# 14_BoardPowerSupply.net
KiCad netlist of a schematic drawn in Altium Designer
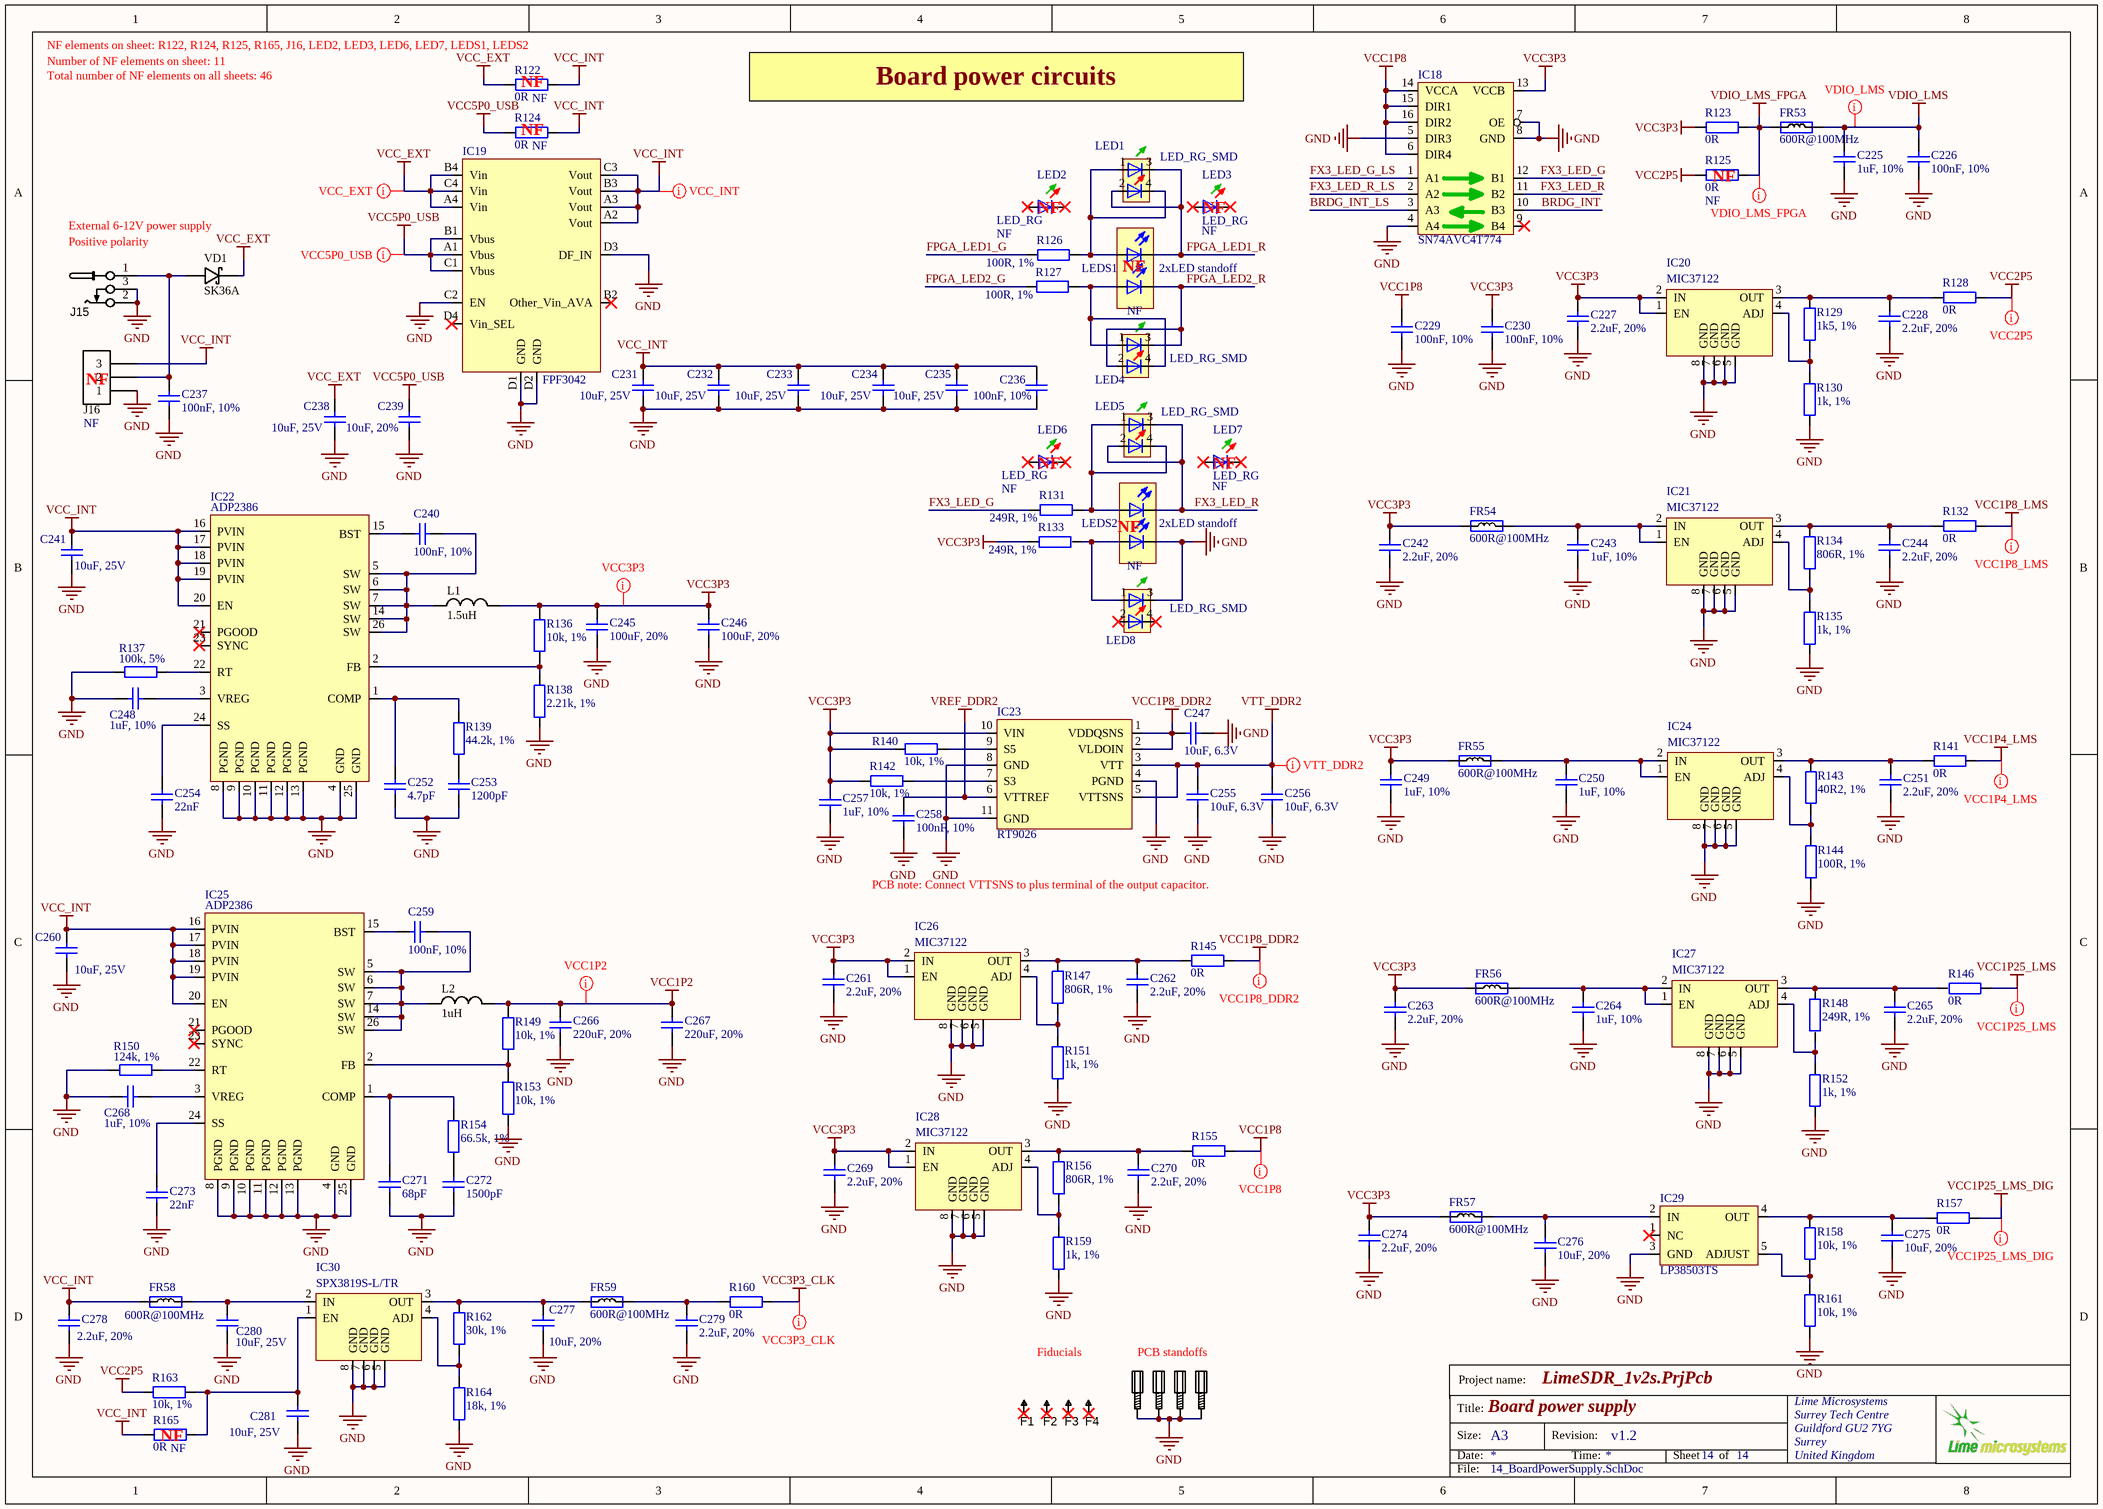
[diagram p0: 14_BoardPowerSupply.SchDoc]

(export (version "E")
  (design (tool "Eeschema 10.0.6"))
  (components
    (comp (ref "C225")
      (value "1uF, 10%")
      (footprint "CAP0402")
      (fields (field (name "MANUFACTURER") "TDK"))
      (libsource (lib "LimeMicroAltiumLib_schLib") (part "Cap_0402"))
    )
    (comp (ref "C226")
      (value "100nF, 10%")
      (footprint "CAP0402")
      (fields
        (field (name "MANUFACTURER") "Murata Electronics")
        (field (name "TOLERANCE") "10 %")
        (field (name "MANUFACTURER PART NUMBER") "GRM155R71C104KA88D")
      )
      (libsource (lib "LimeMicroAltiumLib_schLib") (part "Cap_0402"))
    )
    (comp (ref "C227")
      (value "2.2uF, 20%")
      (footprint "CAP0402")
      (fields (field (name "MANUFACTURER") "TDK Corporation") (field (name "TOLERANCE") "±20%"))
      (libsource (lib "LimeMicroAltiumLib_schLib") (part "Cap_0402"))
    )
    (comp (ref "C228")
      (value "2.2uF, 20%")
      (footprint "CAP0402")
      (fields (field (name "MANUFACTURER") "TDK Corporation") (field (name "TOLERANCE") "±20%"))
      (libsource (lib "LimeMicroAltiumLib_schLib") (part "Cap_0402"))
    )
    (comp (ref "C229")
      (value "100nF, 10%")
      (footprint "LimeMicroAltiumLib_pcbLib:CAP0402")
      (fields
        (field (name "MANUFACTURER") "Murata Electronics")
        (field (name "TOLERANCE") "10 %")
        (field (name "MANUFACTURER PART NUMBER") "GRM155R71C104KA88D")
      )
      (libsource (lib "LimeMicroAltiumLib_schLib") (part "Cap_0402"))
    )
    (comp (ref "C230")
      (value "100nF, 10%")
      (footprint "LimeMicroAltiumLib_pcbLib:CAP0402")
      (fields
        (field (name "MANUFACTURER") "Murata Electronics")
        (field (name "TOLERANCE") "10 %")
        (field (name "MANUFACTURER PART NUMBER") "GRM155R71C104KA88D")
      )
      (libsource (lib "LimeMicroAltiumLib_schLib") (part "Cap_0402"))
    )
    (comp (ref "C231")
      (value "10uF, 25V")
      (footprint "CAP0603")
      (fields
        (field (name "MANUFACTURER") "Murata Electronics North America")
        (field (name "MANUFACTURER PART NUMBER") "GRM188R61E106MA73D")
        (field (name "TOLERANCE") "±20%")
      )
      (libsource (lib "LimeMicroAltiumLib_schLib") (part "Cap_0603"))
    )
    (comp (ref "C232")
      (value "10uF, 25V")
      (footprint "CAP0603")
      (fields
        (field (name "MANUFACTURER") "Murata Electronics North America")
        (field (name "MANUFACTURER PART NUMBER") "GRM188R61E106MA73D")
        (field (name "TOLERANCE") "±20%")
      )
      (libsource (lib "LimeMicroAltiumLib_schLib") (part "Cap_0603"))
    )
    (comp (ref "C233")
      (value "10uF, 25V")
      (footprint "CAP0603")
      (fields
        (field (name "MANUFACTURER") "Murata Electronics North America")
        (field (name "MANUFACTURER PART NUMBER") "GRM188R61E106MA73D")
        (field (name "TOLERANCE") "±20%")
      )
      (libsource (lib "LimeMicroAltiumLib_schLib") (part "Cap_0603"))
    )
    (comp (ref "C234")
      (value "10uF, 25V")
      (footprint "CAP0603")
      (fields
        (field (name "MANUFACTURER") "Murata Electronics North America")
        (field (name "MANUFACTURER PART NUMBER") "GRM188R61E106MA73D")
        (field (name "TOLERANCE") "±20%")
      )
      (libsource (lib "LimeMicroAltiumLib_schLib") (part "Cap_0603"))
    )
    (comp (ref "C235")
      (value "10uF, 25V")
      (footprint "CAP0603")
      (fields
        (field (name "MANUFACTURER") "Murata Electronics North America")
        (field (name "MANUFACTURER PART NUMBER") "GRM188R61E106MA73D")
        (field (name "TOLERANCE") "±20%")
      )
      (libsource (lib "LimeMicroAltiumLib_schLib") (part "Cap_0603"))
    )
    (comp (ref "C236")
      (value "100nF, 10%")
      (footprint "CAP0402")
      (fields
        (field (name "MANUFACTURER") "Murata Electronics")
        (field (name "TOLERANCE") "10 %")
        (field (name "MANUFACTURER PART NUMBER") "GRM155R71C104KA88D")
      )
      (libsource (lib "LimeMicroAltiumLib_schLib") (part "Cap_0402"))
    )
    (comp (ref "C237")
      (value "100nF, 10%")
      (footprint "CAP0402")
      (fields
        (field (name "MANUFACTURER") "Murata Electronics")
        (field (name "TOLERANCE") "10 %")
        (field (name "MANUFACTURER PART NUMBER") "GRM155R71C104KA88D")
      )
      (libsource (lib "LimeMicroAltiumLib_schLib") (part "Cap_0402"))
    )
    (comp (ref "C238")
      (value "10uF, 25V")
      (footprint "CAP0603")
      (fields
        (field (name "MANUFACTURER") "Murata Electronics North America")
        (field (name "MANUFACTURER PART NUMBER") "GRM188R61E106MA73D")
        (field (name "TOLERANCE") "±20%")
      )
      (libsource (lib "LimeMicroAltiumLib_schLib") (part "Cap_0603"))
    )
    (comp (ref "C239")
      (value "10uF, 20%")
      (footprint "CAP0603")
      (fields (field (name "MANUFACTURER") "Yageo") (field (name "TOLERANCE") "±20%"))
      (libsource (lib "LimeMicroAltiumLib_schLib") (part "Cap_0603"))
    )
    (comp (ref "C240")
      (value "100nF, 10%")
      (footprint "CAP0402")
      (fields
        (field (name "MANUFACTURER") "Murata Electronics")
        (field (name "TOLERANCE") "10 %")
        (field (name "MANUFACTURER PART NUMBER") "GRM155R71C104KA88D")
      )
      (libsource (lib "LimeMicroAltiumLib_schLib") (part "Cap_0402"))
    )
    (comp (ref "C241")
      (value "10uF, 25V")
      (footprint "CAP0603")
      (fields
        (field (name "MANUFACTURER") "Murata Electronics North America")
        (field (name "MANUFACTURER PART NUMBER") "GRM188R61E106MA73D")
        (field (name "TOLERANCE") "±20%")
      )
      (libsource (lib "LimeMicroAltiumLib_schLib") (part "Cap_0603"))
    )
    (comp (ref "C242")
      (value "2.2uF, 20%")
      (footprint "CAP0402")
      (fields (field (name "MANUFACTURER") "TDK Corporation") (field (name "TOLERANCE") "±20%"))
      (libsource (lib "LimeMicroAltiumLib_schLib") (part "Cap_0402"))
    )
    (comp (ref "C243")
      (value "1uF, 10%")
      (footprint "CAP0402")
      (fields (field (name "MANUFACTURER") "TDK"))
      (libsource (lib "LimeMicroAltiumLib_schLib") (part "Cap_0402"))
    )
    (comp (ref "C244")
      (value "2.2uF, 20%")
      (footprint "CAP0402")
      (fields (field (name "MANUFACTURER") "TDK Corporation") (field (name "TOLERANCE") "±20%"))
      (libsource (lib "LimeMicroAltiumLib_schLib") (part "Cap_0402"))
    )
    (comp (ref "C245")
      (value "100uF, 20%")
      (footprint "CAP1206")
      (fields (field (name "MANUFACTURER") "Murata Electronics North America"))
      (libsource (lib "LimeFPGAboard_schLib") (part "Cap_1206"))
    )
    (comp (ref "C246")
      (value "100uF, 20%")
      (footprint "CAP1206")
      (fields (field (name "MANUFACTURER") "Murata Electronics North America"))
      (libsource (lib "LimeFPGAboard_schLib") (part "Cap_1206"))
    )
    (comp (ref "C247")
      (value "10uF, 6.3V")
      (footprint "CAP0603")
      (fields (field (name "TOLERANCE") "±20%") (field (name "MANUFACTURER") "Yageo"))
      (libsource (lib "LimeFPGAboard_schLib") (part "Cap_0603"))
    )
    (comp (ref "C248")
      (value "1uF, 10%")
      (footprint "CAP0402")
      (fields (field (name "MANUFACTURER") "TDK"))
      (libsource (lib "LimeMicroAltiumLib_schLib") (part "Cap_0402"))
    )
    (comp (ref "C249")
      (value "1uF, 10%")
      (footprint "CAP0402")
      (fields (field (name "MANUFACTURER") "TDK"))
      (libsource (lib "LimeMicroAltiumLib_schLib") (part "Cap_0402"))
    )
    (comp (ref "C250")
      (value "1uF, 10%")
      (footprint "CAP0402")
      (fields (field (name "MANUFACTURER") "TDK"))
      (libsource (lib "LimeMicroAltiumLib_schLib") (part "Cap_0402"))
    )
    (comp (ref "C251")
      (value "2.2uF, 20%")
      (footprint "CAP0402")
      (fields (field (name "MANUFACTURER") "TDK Corporation") (field (name "TOLERANCE") "±20%"))
      (libsource (lib "LimeMicroAltiumLib_schLib") (part "Cap_0402"))
    )
    (comp (ref "C252")
      (value "4.7pF")
      (footprint "CAP0402")
      (fields (field (name "MANUFACTURER") "Murata Electronics North America"))
      (libsource (lib "LimeMicroAltiumLib_schLib") (part "Cap_0402"))
    )
    (comp (ref "C253")
      (value "1200pF")
      (footprint "CAP0402")
      (fields (field (name "MANUFACTURER") "Kemet") (field (name "TOLERANCE") "±5%"))
      (libsource (lib "LimeMicroAltiumLib_schLib") (part "Cap_0402"))
    )
    (comp (ref "C254")
      (value "22nF")
      (footprint "CAP0402")
      (fields (field (name "TOLERANCE") "±10%") (field (name "MANUFACTURER") "Kemet"))
      (libsource (lib "LimeMicroAltiumLib_schLib") (part "Cap_0402"))
    )
    (comp (ref "C255")
      (value "10uF, 6.3V")
      (footprint "CAP0603")
      (fields (field (name "TOLERANCE") "±20%") (field (name "MANUFACTURER") "Yageo"))
      (libsource (lib "LimeFPGAboard_schLib") (part "Cap_0603"))
    )
    (comp (ref "C256")
      (value "10uF, 6.3V")
      (footprint "CAP0603")
      (fields (field (name "TOLERANCE") "±20%") (field (name "MANUFACTURER") "Yageo"))
      (libsource (lib "LimeFPGAboard_schLib") (part "Cap_0603"))
    )
    (comp (ref "C257")
      (value "1uF, 10%")
      (footprint "CAP0402")
      (fields (field (name "MANUFACTURER") "TDK"))
      (libsource (lib "LimeMicroAltiumLib_schLib") (part "Cap_0402"))
    )
    (comp (ref "C258")
      (value "100nF, 10%")
      (footprint "CAP0402")
      (fields
        (field (name "MANUFACTURER") "Murata Electronics")
        (field (name "TOLERANCE") "10 %")
        (field (name "MANUFACTURER PART NUMBER") "GRM155R71C104KA88D")
      )
      (libsource (lib "LimeMicroAltiumLib_schLib") (part "Cap_0402"))
    )
    (comp (ref "C259")
      (value "100nF, 10%")
      (footprint "CAP0402")
      (fields
        (field (name "MANUFACTURER") "Murata Electronics")
        (field (name "TOLERANCE") "10 %")
        (field (name "MANUFACTURER PART NUMBER") "GRM155R71C104KA88D")
      )
      (libsource (lib "LimeMicroAltiumLib_schLib") (part "Cap_0402"))
    )
    (comp (ref "C260")
      (value "10uF, 25V")
      (footprint "CAP0603")
      (fields
        (field (name "MANUFACTURER") "Murata Electronics North America")
        (field (name "MANUFACTURER PART NUMBER") "GRM188R61E106MA73D")
        (field (name "TOLERANCE") "±20%")
      )
      (libsource (lib "LimeMicroAltiumLib_schLib") (part "Cap_0603"))
    )
    (comp (ref "C261")
      (value "2.2uF, 20%")
      (footprint "CAP0402")
      (fields (field (name "MANUFACTURER") "TDK Corporation") (field (name "TOLERANCE") "±20%"))
      (libsource (lib "LimeMicroAltiumLib_schLib") (part "Cap_0402"))
    )
    (comp (ref "C262")
      (value "2.2uF, 20%")
      (footprint "CAP0402")
      (fields (field (name "MANUFACTURER") "TDK Corporation") (field (name "TOLERANCE") "±20%"))
      (libsource (lib "LimeMicroAltiumLib_schLib") (part "Cap_0402"))
    )
    (comp (ref "C263")
      (value "2.2uF, 20%")
      (footprint "CAP0402")
      (fields (field (name "MANUFACTURER") "TDK Corporation") (field (name "TOLERANCE") "±20%"))
      (libsource (lib "LimeMicroAltiumLib_schLib") (part "Cap_0402"))
    )
    (comp (ref "C264")
      (value "1uF, 10%")
      (footprint "CAP0402")
      (fields (field (name "MANUFACTURER") "TDK"))
      (libsource (lib "LimeMicroAltiumLib_schLib") (part "Cap_0402"))
    )
    (comp (ref "C265")
      (value "2.2uF, 20%")
      (footprint "CAP0402")
      (fields (field (name "MANUFACTURER") "TDK Corporation") (field (name "TOLERANCE") "±20%"))
      (libsource (lib "LimeMicroAltiumLib_schLib") (part "Cap_0402"))
    )
    (comp (ref "C266")
      (value "220uF, 20%")
      (footprint "CAP1206")
      (fields
        (field (name "MANUFACTURER") "Murata Electronics North America")
        (field (name "TOLERANCE") "±20%")
      )
      (libsource (lib "LimeFPGAboard_schLib") (part "Cap_1206"))
    )
    (comp (ref "C267")
      (value "220uF, 20%")
      (footprint "CAP1206")
      (fields
        (field (name "MANUFACTURER") "Murata Electronics North America")
        (field (name "TOLERANCE") "±20%")
      )
      (libsource (lib "LimeFPGAboard_schLib") (part "Cap_1206"))
    )
    (comp (ref "C268")
      (value "1uF, 10%")
      (footprint "CAP0402")
      (fields (field (name "MANUFACTURER") "TDK"))
      (libsource (lib "LimeMicroAltiumLib_schLib") (part "Cap_0402"))
    )
    (comp (ref "C269")
      (value "2.2uF, 20%")
      (footprint "CAP0402")
      (fields (field (name "MANUFACTURER") "TDK Corporation") (field (name "TOLERANCE") "±20%"))
      (libsource (lib "LimeMicroAltiumLib_schLib") (part "Cap_0402"))
    )
    (comp (ref "C270")
      (value "2.2uF, 20%")
      (footprint "CAP0402")
      (fields (field (name "MANUFACTURER") "TDK Corporation") (field (name "TOLERANCE") "±20%"))
      (libsource (lib "LimeMicroAltiumLib_schLib") (part "Cap_0402"))
    )
    (comp (ref "C271")
      (value "68pF")
      (footprint "CAP0402")
      (fields (field (name "TOLERANCE") "±1%") (field (name "MANUFACTURER") "Kemet"))
      (libsource (lib "LimeMicroAltiumLib_schLib") (part "Cap_0402"))
    )
    (comp (ref "C272")
      (value "1500pF")
      (footprint "CAP0402")
      (fields
        (field (name "MANUFACTURER") "Samsung Electro-Mechanics America, Inc.")
        (field (name "TOLERANCE") "±10%")
      )
      (libsource (lib "LimeMicroAltiumLib_schLib") (part "Cap_0402"))
    )
    (comp (ref "C273")
      (value "22nF")
      (footprint "CAP0402")
      (fields (field (name "TOLERANCE") "±10%") (field (name "MANUFACTURER") "Kemet"))
      (libsource (lib "LimeMicroAltiumLib_schLib") (part "Cap_0402"))
    )
    (comp (ref "C274")
      (value "2.2uF, 20%")
      (footprint "CAP0402")
      (fields (field (name "MANUFACTURER") "TDK Corporation") (field (name "TOLERANCE") "±20%"))
      (libsource (lib "LimeMicroAltiumLib_schLib") (part "Cap_0402"))
    )
    (comp (ref "C275")
      (value "10uF, 20%")
      (footprint "CAP0603")
      (fields (field (name "MANUFACTURER") "Yageo") (field (name "TOLERANCE") "±20%"))
      (libsource (lib "LimeMicroAltiumLib_schLib") (part "Cap_0603"))
    )
    (comp (ref "C276")
      (value "10uF, 20%")
      (footprint "CAP0603")
      (fields (field (name "MANUFACTURER") "Yageo") (field (name "TOLERANCE") "±20%"))
      (libsource (lib "LimeMicroAltiumLib_schLib") (part "Cap_0603"))
    )
    (comp (ref "C277")
      (value "10uF, 20%")
      (footprint "CAP0603")
      (fields (field (name "MANUFACTURER") "Yageo") (field (name "TOLERANCE") "±20%"))
      (libsource (lib "LimeMicroAltiumLib_schLib") (part "Cap_0603"))
    )
    (comp (ref "C278")
      (value "2.2uF, 20%")
      (footprint "CAP0402")
      (fields (field (name "MANUFACTURER") "TDK Corporation") (field (name "TOLERANCE") "±20%"))
      (libsource (lib "LimeMicroAltiumLib_schLib") (part "Cap_0402"))
    )
    (comp (ref "C279")
      (value "2.2uF, 20%")
      (footprint "CAP0402")
      (fields (field (name "MANUFACTURER") "TDK Corporation") (field (name "TOLERANCE") "±20%"))
      (libsource (lib "LimeMicroAltiumLib_schLib") (part "Cap_0402"))
    )
    (comp (ref "C280")
      (value "10uF, 25V")
      (footprint "CAP0603")
      (fields
        (field (name "MANUFACTURER") "Murata Electronics North America")
        (field (name "MANUFACTURER PART NUMBER") "GRM188R61E106MA73D")
        (field (name "TOLERANCE") "±20%")
      )
      (libsource (lib "LimeMicroAltiumLib_schLib") (part "Cap_0603"))
    )
    (comp (ref "C281")
      (value "10uF, 25V")
      (footprint "CAP0603")
      (fields
        (field (name "MANUFACTURER") "Murata Electronics North America")
        (field (name "MANUFACTURER PART NUMBER") "GRM188R61E106MA73D")
        (field (name "TOLERANCE") "±20%")
      )
      (libsource (lib "LimeMicroAltiumLib_schLib") (part "Cap_0603"))
    )
    (comp (ref "F1")
      (value "Fiducial")
      (footprint "Fiducial")
      (libsource (lib "VGTU_Altium_lib") (part "Fiducial"))
    )
    (comp (ref "F2")
      (value "Fiducial")
      (footprint "Fiducial")
      (libsource (lib "VGTU_Altium_lib") (part "Fiducial"))
    )
    (comp (ref "F3")
      (value "Fiducial")
      (footprint "Fiducial")
      (libsource (lib "VGTU_Altium_lib") (part "Fiducial"))
    )
    (comp (ref "F4")
      (value "Fiducial")
      (footprint "Fiducial")
      (libsource (lib "VGTU_Altium_lib") (part "Fiducial"))
    )
    (comp (ref "FR53")
      (value "600R@100MHz")
      (footprint "RES0805")
      (fields (field (name "MANUFACTURER") "TDK Corporation"))
      (libsource (lib "LimeMicroAltiumLib_schLib") (part "Ferrite"))
    )
    (comp (ref "FR54")
      (value "600R@100MHz")
      (footprint "RES0805")
      (fields (field (name "MANUFACTURER") "TDK Corporation"))
      (libsource (lib "LimeMicroAltiumLib_schLib") (part "Ferrite"))
    )
    (comp (ref "FR55")
      (value "600R@100MHz")
      (footprint "RES0805")
      (fields (field (name "MANUFACTURER") "TDK Corporation"))
      (libsource (lib "LimeMicroAltiumLib_schLib") (part "Ferrite"))
    )
    (comp (ref "FR56")
      (value "600R@100MHz")
      (footprint "RES0805")
      (fields (field (name "MANUFACTURER") "TDK Corporation"))
      (libsource (lib "LimeMicroAltiumLib_schLib") (part "Ferrite"))
    )
    (comp (ref "FR57")
      (value "600R@100MHz")
      (footprint "RES0805")
      (fields (field (name "MANUFACTURER") "TDK Corporation"))
      (libsource (lib "LimeMicroAltiumLib_schLib") (part "Ferrite"))
    )
    (comp (ref "FR58")
      (value "600R@100MHz")
      (footprint "RES0805")
      (fields (field (name "MANUFACTURER") "TDK Corporation"))
      (libsource (lib "LimeMicroAltiumLib_schLib") (part "Ferrite"))
    )
    (comp (ref "FR59")
      (value "600R@100MHz")
      (footprint "RES0805")
      (fields (field (name "MANUFACTURER") "TDK Corporation"))
      (libsource (lib "LimeMicroAltiumLib_schLib") (part "Ferrite"))
    )
    (comp (ref "IC18")
      (value "SN74AVC4T774")
      (footprint "LimeMicroAltiumLib_pcbLib:SN74AVC4T774")
      (fields (field (name "MANUFACTURER") "Texas Instruments"))
      (libsource (lib "LimeMicroAltiumLib_schLib") (part "SN74AVC4T774"))
    )
    (comp (ref "IC19")
      (value "FPF3042")
      (footprint "FPF3042")
      (fields (field (name "MANUFACTURER") "Fairchild Semiconductor"))
      (libsource (lib "LimeMicroAltiumLib_schLib") (part "FPF3042"))
    )
    (comp (ref "IC20")
      (value "MIC37122")
      (footprint "MIC37122YM TR_SO8")
      (fields (field (name "MANUFACTURER") "Microchip Technology"))
      (libsource (lib "LimeMicroAltiumLib_schLib") (part "MIC37122"))
    )
    (comp (ref "IC21")
      (value "MIC37122")
      (footprint "MIC37122YM TR_SO8")
      (fields (field (name "MANUFACTURER") "Microchip Technology"))
      (libsource (lib "LimeMicroAltiumLib_schLib") (part "MIC37122"))
    )
    (comp (ref "IC22")
      (value "ADP2386")
      (footprint "ADP2386")
      (fields
        (field (name "MANUFACTURER PART NUMBER") "ADP2386ACPZN-R7")
        (field (name "MANUFACTURER") "Analog Devices Inc.")
      )
      (libsource (lib "LimeMicroAltiumLib_schLib") (part "ADP2386"))
    )
    (comp (ref "IC23")
      (value "RT9026")
      (footprint "MSOP10")
      (fields (field (name "MANUFACTURER") "Richtek USA Inc."))
      (libsource (lib "LimeMicroAltiumLib_schLib") (part "RT9026"))
    )
    (comp (ref "IC24")
      (value "MIC37122")
      (footprint "MIC37122YM TR_SO8")
      (fields (field (name "MANUFACTURER") "Microchip Technology"))
      (libsource (lib "LimeMicroAltiumLib_schLib") (part "MIC37122"))
    )
    (comp (ref "IC25")
      (value "ADP2386")
      (footprint "ADP2386")
      (fields (field (name "MANUFACTURER") "Analog Devices Inc."))
      (libsource (lib "LimeMicroAltiumLib_schLib") (part "ADP2386"))
    )
    (comp (ref "IC26")
      (value "MIC37122")
      (footprint "MIC37122YM TR_SO8")
      (fields (field (name "MANUFACTURER") "Microchip Technology"))
      (libsource (lib "LimeMicroAltiumLib_schLib") (part "MIC37122"))
    )
    (comp (ref "IC27")
      (value "MIC37122")
      (footprint "MIC37122YM TR_SO8")
      (fields (field (name "MANUFACTURER") "Microchip Technology"))
      (libsource (lib "LimeMicroAltiumLib_schLib") (part "MIC37122"))
    )
    (comp (ref "IC28")
      (value "MIC37122")
      (footprint "MIC37122YM TR_SO8")
      (fields (field (name "MANUFACTURER") "Microchip Technology"))
      (libsource (lib "LimeMicroAltiumLib_schLib") (part "MIC37122"))
    )
    (comp (ref "IC29")
      (value "LP38503TS")
      (footprint "TO-263-5_v2")
      (fields
        (field (name "MANUFACTURER PART NUMBER") "LP38503TS-ADJ/NOPB")
        (field (name "MANUFACTURER") "Texas Instruments")
      )
      (libsource (lib "LimeMicroAltiumLib_schLib") (part "LP38503TS"))
    )
    (comp (ref "IC30")
      (value "SPX3819S-L/TR")
      (footprint "MIC37122YM TR_SO8")
      (fields (field (name "MANUFACTURER") "Exar Corporation"))
      (libsource (lib "LimeMicroAltiumLib_schLib") (part "MIC37122"))
    )
    (comp (ref "J15")
      (value "CONN_PWR_JACK_2.1x5.5mm")
      (footprint "CONN_PWR_JACK_v3")
      (description "Power Connector, THT, 2.1mm ID, 5.5mm OD")
      (fields (field (name "MANUFACTURER") "CUI Inc."))
      (libsource (lib "LimeFPGAboard_schLib") (part "CONN_PWR_JACK_2.1x5.5mm"))
    )
    (comp (ref "J16")
      (value "Header 3x1 pin")
      (footprint "HDR_1x3")
      (description "Header, 3-pin")
      (fields (field (name "ASSEMBLY INFO") "NF") (field (name "MANUFACTURER") "Amphenol FCI"))
      (libsource (lib "LimeMicroAltiumLib_schLib") (part "Header3P"))
    )
    (comp (ref "L1")
      (value "1.5uH")
      (footprint "FDVE1040_TOKO_INDUCTOR")
      (fields (field (name "MANUFACTURER") "Vishay Dale") (field (name "TOLERANCE") "±20%"))
      (libsource (lib "LimeMicroAltiumLib_schLib") (part "Inductor_0603"))
    )
    (comp (ref "L2")
      (value "1uH")
      (footprint "FDVE1040_TOKO_INDUCTOR")
      (fields (field (name "TOLERANCE") "±20%") (field (name "MANUFACTURER") "Vishay Dale"))
      (libsource (lib "LimeMicroAltiumLib_schLib") (part "Inductor_0603"))
    )
    (comp (ref "LED1")
      (value "LED_RG_SMD")
      (footprint "LED-2x0603")
      (fields (field (name "MANUFACTURER") "Avago Technologies US Inc."))
      (libsource (lib "LimeMicroAltiumLib_schLib") (part "LED_green_red_SMD"))
    )
    (comp (ref "LED2")
      (value "LED_RG")
      (fields
        (field (name "MANUFACTURER") "Visual Communications Company - VCC")
        (field (name "ASSEMBLY INFO") "NF")
      )
      (libsource (lib "LimeMicroAltiumLib_schLib") (part "LED_green_red"))
    )
    (comp (ref "LED3")
      (value "LED_RG")
      (fields
        (field (name "MANUFACTURER") "Visual Communications Company - VCC")
        (field (name "ASSEMBLY INFO") "NF")
      )
      (libsource (lib "LimeMicroAltiumLib_schLib") (part "LED_green_red"))
    )
    (comp (ref "LED4")
      (value "LED_RG_SMD")
      (footprint "LED-2x0603")
      (fields (field (name "MANUFACTURER") "Avago Technologies US Inc."))
      (libsource (lib "LimeMicroAltiumLib_schLib") (part "LED_green_red_SMD"))
    )
    (comp (ref "LED5")
      (value "LED_RG_SMD")
      (footprint "LED-2x0603")
      (fields (field (name "MANUFACTURER") "Avago Technologies US Inc."))
      (libsource (lib "LimeMicroAltiumLib_schLib") (part "LED_green_red_SMD"))
    )
    (comp (ref "LED6")
      (value "LED_RG")
      (fields
        (field (name "MANUFACTURER") "Visual Communications Company - VCC")
        (field (name "ASSEMBLY INFO") "NF")
      )
      (libsource (lib "LimeMicroAltiumLib_schLib") (part "LED_green_red"))
    )
    (comp (ref "LED7")
      (value "LED_RG")
      (fields
        (field (name "MANUFACTURER") "Visual Communications Company - VCC")
        (field (name "ASSEMBLY INFO") "NF")
      )
      (libsource (lib "LimeMicroAltiumLib_schLib") (part "LED_green_red"))
    )
    (comp (ref "LED8")
      (value "LED_RG_SMD")
      (footprint "LED-2x0603")
      (fields (field (name "MANUFACTURER") "Avago Technologies US Inc."))
      (libsource (lib "LimeMicroAltiumLib_schLib") (part "LED_green_red_SMD"))
    )
    (comp (ref "LEDS1")
      (value "2xLED standoff")
      (footprint "LED_STANDOFF_H-201C")
      (fields (field (name "MANUFACTURER") "Bivar Inc.") (field (name "ASSEMBLY INFO") "NF"))
      (libsource (lib "LimeMicroAltiumLib_schLib") (part "LEDx2_STANDOFF"))
    )
    (comp (ref "LEDS2")
      (value "2xLED standoff")
      (footprint "LED_STANDOFF_H-201C")
      (fields (field (name "MANUFACTURER") "Bivar Inc.") (field (name "ASSEMBLY INFO") "NF"))
      (libsource (lib "LimeMicroAltiumLib_schLib") (part "LEDx2_STANDOFF"))
    )
    (comp (ref "MECH1")
      (value "# pcs.")
      (footprint "PCB_standoff")
      (description "STANDOFF M/F MET 5MM HEX 10MM L")
      (fields
        (field (name "MANUFACTURER") "FIX&FASTEN")
        (field (name "MANUFACTURER PART NUMBER") "FIX-MAE-5TV")
      )
      (libsource (lib "LimeMicroAltiumLib_schLib") (part "STANDOFF_M-F_THREADED_M3x8x10mm_HEX_5mm dia"))
    )
    (comp (ref "MECH2")
      (value "# pcs.")
      (footprint "PCB_standoff")
      (description "STANDOFF M/F MET 5MM HEX 10MM L")
      (fields
        (field (name "MANUFACTURER") "FIX&FASTEN")
        (field (name "MANUFACTURER PART NUMBER") "FIX-MAE-5TV")
      )
      (libsource (lib "LimeMicroAltiumLib_schLib") (part "STANDOFF_M-F_THREADED_M3x8x10mm_HEX_5mm dia"))
    )
    (comp (ref "MECH3")
      (value "# pcs.")
      (footprint "PCB_standoff")
      (description "STANDOFF M/F MET 5MM HEX 10MM L")
      (fields
        (field (name "MANUFACTURER") "FIX&FASTEN")
        (field (name "MANUFACTURER PART NUMBER") "FIX-MAE-5TV")
      )
      (libsource (lib "LimeMicroAltiumLib_schLib") (part "STANDOFF_M-F_THREADED_M3x8x10mm_HEX_5mm dia"))
    )
    (comp (ref "MECH4")
      (value "# pcs.")
      (footprint "PCB_standoff")
      (description "STANDOFF M/F MET 5MM HEX 10MM L")
      (fields
        (field (name "MANUFACTURER") "FIX&FASTEN")
        (field (name "MANUFACTURER PART NUMBER") "FIX-MAE-5TV")
      )
      (libsource (lib "LimeMicroAltiumLib_schLib") (part "STANDOFF_M-F_THREADED_M3x8x10mm_HEX_5mm dia"))
    )
    (comp (ref "R122")
      (value "0R")
      (footprint "RES0402")
      (fields
        (field (name "ASSEMBLY INFO") "NF")
        (field (name "MANUFACTURER") "Yageo")
        (field (name "TOLERANCE") "Jumper")
      )
      (libsource (lib "LimeMicroAltiumLib_schLib") (part "Res_0402"))
    )
    (comp (ref "R123")
      (value "0R")
      (footprint "RES0402")
      (fields (field (name "MANUFACTURER") "Yageo") (field (name "TOLERANCE") "Jumper"))
      (libsource (lib "LimeMicroAltiumLib_schLib") (part "Res_0402"))
    )
    (comp (ref "R124")
      (value "0R")
      (footprint "RES0402")
      (fields
        (field (name "ASSEMBLY INFO") "NF")
        (field (name "MANUFACTURER") "Yageo")
        (field (name "TOLERANCE") "Jumper")
      )
      (libsource (lib "LimeMicroAltiumLib_schLib") (part "Res_0402"))
    )
    (comp (ref "R125")
      (value "0R")
      (footprint "RES0402")
      (fields
        (field (name "ASSEMBLY INFO") "NF")
        (field (name "MANUFACTURER") "Yageo")
        (field (name "TOLERANCE") "Jumper")
      )
      (libsource (lib "LimeMicroAltiumLib_schLib") (part "Res_0402"))
    )
    (comp (ref "R126")
      (value "100R, 1%")
      (footprint "RES0402")
      (fields (field (name "TOLERANCE") "±1%") (field (name "MANUFACTURER") "Stackpole Electronics Inc"))
      (libsource (lib "LimeMicroAltiumLib_schLib") (part "Res_0402"))
    )
    (comp (ref "R127")
      (value "100R, 1%")
      (footprint "RES0402")
      (fields (field (name "TOLERANCE") "±1%") (field (name "MANUFACTURER") "Stackpole Electronics Inc"))
      (libsource (lib "LimeMicroAltiumLib_schLib") (part "Res_0402"))
    )
    (comp (ref "R128")
      (value "0R")
      (footprint "RES0402")
      (fields (field (name "MANUFACTURER") "Yageo") (field (name "TOLERANCE") "Jumper"))
      (libsource (lib "LimeMicroAltiumLib_schLib") (part "Res_0402"))
    )
    (comp (ref "R129")
      (value "1k5, 1%")
      (footprint "RES0402")
      (fields (field (name "MANUFACTURER") "Yageo") (field (name "TOLERANCE") "±1%"))
      (libsource (lib "LimeMicroAltiumLib_schLib") (part "Res_0402"))
    )
    (comp (ref "R130")
      (value "1k, 1%")
      (footprint "RES0402")
      (fields (field (name "MANUFACTURER") "Stackpole Electronics Inc") (field (name "TOLERANCE") "±1%"))
      (libsource (lib "LimeMicroAltiumLib_schLib") (part "Res_0402"))
    )
    (comp (ref "R131")
      (value "249R, 1%")
      (footprint "RES0402")
      (fields (field (name "MANUFACTURER") "Stackpole Electronics Inc") (field (name "TOLERANCE") "±1%"))
      (libsource (lib "LimeMicroAltiumLib_schLib") (part "Res_0402"))
    )
    (comp (ref "R132")
      (value "0R")
      (footprint "RES0402")
      (fields (field (name "MANUFACTURER") "Yageo") (field (name "TOLERANCE") "Jumper"))
      (libsource (lib "LimeMicroAltiumLib_schLib") (part "Res_0402"))
    )
    (comp (ref "R133")
      (value "249R, 1%")
      (footprint "RES0402")
      (fields (field (name "MANUFACTURER") "Stackpole Electronics Inc") (field (name "TOLERANCE") "±1%"))
      (libsource (lib "LimeMicroAltiumLib_schLib") (part "Res_0402"))
    )
    (comp (ref "R134")
      (value "806R, 1%")
      (footprint "RES0402")
      (fields (field (name "TOLERANCE") "±1%") (field (name "MANUFACTURER") "Stackpole Electronics Inc"))
      (libsource (lib "LimeMicroAltiumLib_schLib") (part "Res_0402"))
    )
    (comp (ref "R135")
      (value "1k, 1%")
      (footprint "RES0402")
      (fields (field (name "MANUFACTURER") "Stackpole Electronics Inc") (field (name "TOLERANCE") "±1%"))
      (libsource (lib "LimeMicroAltiumLib_schLib") (part "Res_0402"))
    )
    (comp (ref "R136")
      (value "10k, 1%")
      (footprint "RES0402")
      (fields (field (name "MANUFACTURER") "Yageo") (field (name "TOLERANCE") "±1%"))
      (libsource (lib "LimeMicroAltiumLib_schLib") (part "Res_0402"))
    )
    (comp (ref "R137")
      (value "100k, 5%")
      (footprint "RES0402")
      (fields
        (field (name "MANUFACTURER") "Panasonic Electronic Components")
        (field (name "MANUFACTURER PART NUMBER") "ERJ-2GEJ104X")
        (field (name "TOLERANCE") "±5%")
      )
      (libsource (lib "LimeMicroAltiumLib_schLib") (part "Res_0402"))
    )
    (comp (ref "R138")
      (value "2.21k, 1%")
      (footprint "RES0402")
      (fields (field (name "MANUFACTURER") "Stackpole Electronics Inc.") (field (name "TOLERANCE") "±1%"))
      (libsource (lib "LimeMicroAltiumLib_schLib") (part "Res_0402"))
    )
    (comp (ref "R139")
      (value "44.2k, 1%")
      (footprint "RES0402")
      (fields
        (field (name "TOLERANCE") "±1%")
        (field (name "MANUFACTURER") "Panasonic Electronic Components")
      )
      (libsource (lib "LimeMicroAltiumLib_schLib") (part "Res_0402"))
    )
    (comp (ref "R140")
      (value "10k, 1%")
      (footprint "RES0402")
      (fields (field (name "MANUFACTURER") "Yageo") (field (name "TOLERANCE") "±1%"))
      (libsource (lib "LimeMicroAltiumLib_schLib") (part "Res_0402"))
    )
    (comp (ref "R141")
      (value "0R")
      (footprint "RES0402")
      (fields (field (name "MANUFACTURER") "Yageo") (field (name "TOLERANCE") "Jumper"))
      (libsource (lib "LimeMicroAltiumLib_schLib") (part "Res_0402"))
    )
    (comp (ref "R142")
      (value "10k, 1%")
      (footprint "RES0402")
      (fields (field (name "MANUFACTURER") "Yageo") (field (name "TOLERANCE") "±1%"))
      (libsource (lib "LimeMicroAltiumLib_schLib") (part "Res_0402"))
    )
    (comp (ref "R143")
      (value "40R2, 1%")
      (footprint "RES0402")
      (fields (field (name "MANUFACTURER") "Stackpole Electronics Inc") (field (name "TOLERANCE") "±1%"))
      (libsource (lib "LimeMicroAltiumLib_schLib") (part "Res_0402"))
    )
    (comp (ref "R144")
      (value "100R, 1%")
      (footprint "RES0402")
      (fields (field (name "TOLERANCE") "±1%") (field (name "MANUFACTURER") "Stackpole Electronics Inc"))
      (libsource (lib "LimeMicroAltiumLib_schLib") (part "Res_0402"))
    )
    (comp (ref "R145")
      (value "0R")
      (footprint "RES0402")
      (fields (field (name "MANUFACTURER") "Yageo") (field (name "TOLERANCE") "Jumper"))
      (libsource (lib "LimeMicroAltiumLib_schLib") (part "Res_0402"))
    )
    (comp (ref "R146")
      (value "0R")
      (footprint "RES0402")
      (fields (field (name "MANUFACTURER") "Yageo") (field (name "TOLERANCE") "Jumper"))
      (libsource (lib "LimeMicroAltiumLib_schLib") (part "Res_0402"))
    )
    (comp (ref "R147")
      (value "806R, 1%")
      (footprint "RES0402")
      (fields (field (name "TOLERANCE") "±1%") (field (name "MANUFACTURER") "Stackpole Electronics Inc"))
      (libsource (lib "LimeMicroAltiumLib_schLib") (part "Res_0402"))
    )
    (comp (ref "R148")
      (value "249R, 1%")
      (footprint "RES0402")
      (fields (field (name "MANUFACTURER") "Stackpole Electronics Inc") (field (name "TOLERANCE") "±1%"))
      (libsource (lib "LimeMicroAltiumLib_schLib") (part "Res_0402"))
    )
    (comp (ref "R149")
      (value "10k, 1%")
      (footprint "RES0402")
      (fields (field (name "MANUFACTURER") "Yageo") (field (name "TOLERANCE") "±1%"))
      (libsource (lib "LimeMicroAltiumLib_schLib") (part "Res_0402"))
    )
    (comp (ref "R150")
      (value "124k, 1%")
      (footprint "RES0402")
      (fields
        (field (name "MANUFACTURER") "Panasonic Electronic Components")
        (field (name "TOLERANCE") "±1%")
      )
      (libsource (lib "LimeMicroAltiumLib_schLib") (part "Res_0402"))
    )
    (comp (ref "R151")
      (value "1k, 1%")
      (footprint "RES0402")
      (fields (field (name "MANUFACTURER") "Stackpole Electronics Inc") (field (name "TOLERANCE") "±1%"))
      (libsource (lib "LimeMicroAltiumLib_schLib") (part "Res_0402"))
    )
    (comp (ref "R152")
      (value "1k, 1%")
      (footprint "RES0402")
      (fields (field (name "MANUFACTURER") "Stackpole Electronics Inc") (field (name "TOLERANCE") "±1%"))
      (libsource (lib "LimeMicroAltiumLib_schLib") (part "Res_0402"))
    )
    (comp (ref "R153")
      (value "10k, 1%")
      (footprint "RES0402")
      (fields (field (name "MANUFACTURER") "Yageo") (field (name "TOLERANCE") "±1%"))
      (libsource (lib "LimeMicroAltiumLib_schLib") (part "Res_0402"))
    )
    (comp (ref "R154")
      (value "66.5k, 1%")
      (footprint "RES0402")
      (fields
        (field (name "MANUFACTURER") "Panasonic Electronic Components")
        (field (name "TOLERANCE") "±1%")
      )
      (libsource (lib "LimeMicroAltiumLib_schLib") (part "Res_0402"))
    )
    (comp (ref "R155")
      (value "0R")
      (footprint "RES0402")
      (fields (field (name "MANUFACTURER") "Yageo") (field (name "TOLERANCE") "Jumper"))
      (libsource (lib "LimeMicroAltiumLib_schLib") (part "Res_0402"))
    )
    (comp (ref "R156")
      (value "806R, 1%")
      (footprint "RES0402")
      (fields (field (name "TOLERANCE") "±1%") (field (name "MANUFACTURER") "Stackpole Electronics Inc"))
      (libsource (lib "LimeMicroAltiumLib_schLib") (part "Res_0402"))
    )
    (comp (ref "R157")
      (value "0R")
      (footprint "RES0402")
      (fields (field (name "MANUFACTURER") "Yageo") (field (name "TOLERANCE") "Jumper"))
      (libsource (lib "LimeMicroAltiumLib_schLib") (part "Res_0402"))
    )
    (comp (ref "R158")
      (value "10k, 1%")
      (footprint "RES0402")
      (fields (field (name "MANUFACTURER") "Yageo") (field (name "TOLERANCE") "±1%"))
      (libsource (lib "LimeMicroAltiumLib_schLib") (part "Res_0402"))
    )
    (comp (ref "R159")
      (value "1k, 1%")
      (footprint "RES0402")
      (fields (field (name "MANUFACTURER") "Stackpole Electronics Inc") (field (name "TOLERANCE") "±1%"))
      (libsource (lib "LimeMicroAltiumLib_schLib") (part "Res_0402"))
    )
    (comp (ref "R160")
      (value "0R")
      (footprint "RES0402")
      (fields (field (name "MANUFACTURER") "Yageo") (field (name "TOLERANCE") "Jumper"))
      (libsource (lib "LimeMicroAltiumLib_schLib") (part "Res_0402"))
    )
    (comp (ref "R161")
      (value "10k, 1%")
      (footprint "RES0402")
      (fields (field (name "MANUFACTURER") "Yageo") (field (name "TOLERANCE") "±1%"))
      (libsource (lib "LimeMicroAltiumLib_schLib") (part "Res_0402"))
    )
    (comp (ref "R162")
      (value "30k, 1%")
      (footprint "RES0402")
      (fields
        (field (name "MANUFACTURER") "Vishay Dale")
        (field (name "MANUFACTURER PART NUMBER") "CRCW040230K0FKED")
        (field (name "TOLERANCE") "±1%")
      )
      (libsource (lib "LimeMicroAltiumLib_schLib") (part "Res_0402"))
    )
    (comp (ref "R163")
      (value "10k, 1%")
      (footprint "RES0402")
      (fields (field (name "MANUFACTURER") "Yageo") (field (name "TOLERANCE") "±1%"))
      (libsource (lib "LimeMicroAltiumLib_schLib") (part "Res_0402"))
    )
    (comp (ref "R164")
      (value "18k, 1%")
      (footprint "RES0402")
      (fields
        (field (name "TOLERANCE") "±1%")
        (field (name "MANUFACTURER PART NUMBER") "CRCW040218K0FKED")
        (field (name "MANUFACTURER") "Vishay Dale")
      )
      (libsource (lib "LimeMicroAltiumLib_schLib") (part "Res_0402"))
    )
    (comp (ref "R165")
      (value "0R")
      (footprint "RES0402")
      (fields
        (field (name "ASSEMBLY INFO") "NF")
        (field (name "MANUFACTURER") "Yageo")
        (field (name "TOLERANCE") "Jumper")
      )
      (libsource (lib "LimeMicroAltiumLib_schLib") (part "Res_0402"))
    )
    (comp (ref "VD1")
      (value "SK36A")
      (footprint "DIODE_SMB")
      (description "Diode Schottky SMD SOD-523F")
      (fields (field (name "MANUFACTURER") "Micro Commercial Co"))
      (libsource (lib "LimeMicroAltiumLib_schLib") (part "DIODE_SCHOTTKY_SOD-523F"))
    )
  )
  (nets
    (net (code "1") (name "/BRDG_INT") (class "Default")
      (node (ref "IC18") (pin "10") (pinfunction "B3_10") (pintype "passive"))
    )
    (net (code "2") (name "/BRDG_INT_LS") (class "Default")
      (node (ref "IC18") (pin "3") (pinfunction "A3_3") (pintype "passive"))
    )
    (net (code "3") (name "/FPGA_LED1_G") (class "Default")
      (node (ref "R126") (pin "1") (pinfunction "1_1") (pintype "passive"))
    )
    (net (code "4") (name "/FPGA_LED1_R") (class "Default")
      (node (ref "LED1") (pin "2") (pinfunction "2_2") (pintype "power_in"))
      (node (ref "LED1") (pin "3") (pinfunction "3_3") (pintype "power_in"))
      (node (ref "LEDS1") (pin "K1") (pinfunction "C_K1") (pintype "power_in"))
    )
    (net (code "5") (name "/FPGA_LED2_G") (class "Default")
      (node (ref "R127") (pin "1") (pinfunction "1_1") (pintype "passive"))
    )
    (net (code "6") (name "/FPGA_LED2_R") (class "Default")
      (node (ref "LED4") (pin "2") (pinfunction "2_2") (pintype "power_in"))
      (node (ref "LED4") (pin "3") (pinfunction "3_3") (pintype "power_in"))
      (node (ref "LEDS1") (pin "K2") (pinfunction "C_K2") (pintype "power_in"))
    )
    (net (code "7") (name "/FX3_LED_G") (class "Default")
      (node (ref "IC18") (pin "12") (pinfunction "B1_12") (pintype "passive"))
      (node (ref "R131") (pin "1") (pinfunction "1_1") (pintype "passive"))
    )
    (net (code "8") (name "/FX3_LED_G_LS") (class "Default")
      (node (ref "IC18") (pin "1") (pinfunction "A1_1") (pintype "passive"))
    )
    (net (code "9") (name "/FX3_LED_R") (class "Default")
      (node (ref "IC18") (pin "11") (pinfunction "B2_11") (pintype "passive"))
      (node (ref "LED5") (pin "2") (pinfunction "2_2") (pintype "power_in"))
      (node (ref "LED5") (pin "3") (pinfunction "3_3") (pintype "power_in"))
      (node (ref "LEDS2") (pin "K1") (pinfunction "C_K1") (pintype "power_in"))
    )
    (net (code "10") (name "/FX3_LED_R_LS") (class "Default")
      (node (ref "IC18") (pin "2") (pinfunction "A2_2") (pintype "passive"))
    )
    (net (code "11") (name "GND") (class "Default")
      (node (ref "C225") (pin "1") (pinfunction "1_1") (pintype "passive"))
      (node (ref "C226") (pin "2") (pinfunction "2_2") (pintype "passive"))
      (node (ref "C227") (pin "1") (pinfunction "1_1") (pintype "passive"))
      (node (ref "C228") (pin "1") (pinfunction "1_1") (pintype "passive"))
      (node (ref "C229") (pin "1") (pinfunction "1_1") (pintype "passive"))
      (node (ref "C230") (pin "1") (pinfunction "1_1") (pintype "passive"))
      (node (ref "C231") (pin "1") (pinfunction "1_1") (pintype "passive"))
      (node (ref "C232") (pin "1") (pinfunction "1_1") (pintype "passive"))
      (node (ref "C233") (pin "1") (pinfunction "1_1") (pintype "passive"))
      (node (ref "C234") (pin "1") (pinfunction "1_1") (pintype "passive"))
      (node (ref "C235") (pin "1") (pinfunction "1_1") (pintype "passive"))
      (node (ref "C236") (pin "2") (pinfunction "2_2") (pintype "passive"))
      (node (ref "C237") (pin "2") (pinfunction "2_2") (pintype "passive"))
      (node (ref "C238") (pin "1") (pinfunction "1_1") (pintype "passive"))
      (node (ref "C239") (pin "1") (pinfunction "1_1") (pintype "passive"))
      (node (ref "C241") (pin "1") (pinfunction "1_1") (pintype "passive"))
      (node (ref "C242") (pin "1") (pinfunction "1_1") (pintype "passive"))
      (node (ref "C243") (pin "1") (pinfunction "1_1") (pintype "passive"))
      (node (ref "C244") (pin "1") (pinfunction "1_1") (pintype "passive"))
      (node (ref "C245") (pin "1") (pinfunction "1_1") (pintype "passive"))
      (node (ref "C246") (pin "1") (pinfunction "1_1") (pintype "passive"))
      (node (ref "C247") (pin "1") (pinfunction "1_1") (pintype "passive"))
      (node (ref "C248") (pin "2") (pinfunction "2_2") (pintype "passive"))
      (node (ref "C249") (pin "1") (pinfunction "1_1") (pintype "passive"))
      (node (ref "C250") (pin "1") (pinfunction "1_1") (pintype "passive"))
      (node (ref "C251") (pin "1") (pinfunction "1_1") (pintype "passive"))
      (node (ref "C252") (pin "2") (pinfunction "2_2") (pintype "passive"))
      (node (ref "C253") (pin "2") (pinfunction "2_2") (pintype "passive"))
      (node (ref "C254") (pin "2") (pinfunction "2_2") (pintype "passive"))
      (node (ref "C255") (pin "1") (pinfunction "1_1") (pintype "passive"))
      (node (ref "C256") (pin "1") (pinfunction "1_1") (pintype "passive"))
      (node (ref "C257") (pin "1") (pinfunction "1_1") (pintype "passive"))
      (node (ref "C258") (pin "2") (pinfunction "2_2") (pintype "passive"))
      (node (ref "C260") (pin "1") (pinfunction "1_1") (pintype "passive"))
      (node (ref "C261") (pin "1") (pinfunction "1_1") (pintype "passive"))
      (node (ref "C262") (pin "1") (pinfunction "1_1") (pintype "passive"))
      (node (ref "C263") (pin "1") (pinfunction "1_1") (pintype "passive"))
      (node (ref "C264") (pin "1") (pinfunction "1_1") (pintype "passive"))
      (node (ref "C265") (pin "1") (pinfunction "1_1") (pintype "passive"))
      (node (ref "C266") (pin "1") (pinfunction "1_1") (pintype "passive"))
      (node (ref "C267") (pin "1") (pinfunction "1_1") (pintype "passive"))
      (node (ref "C268") (pin "2") (pinfunction "2_2") (pintype "passive"))
      (node (ref "C269") (pin "1") (pinfunction "1_1") (pintype "passive"))
      (node (ref "C270") (pin "1") (pinfunction "1_1") (pintype "passive"))
      (node (ref "C271") (pin "2") (pinfunction "2_2") (pintype "passive"))
      (node (ref "C272") (pin "2") (pinfunction "2_2") (pintype "passive"))
      (node (ref "C273") (pin "2") (pinfunction "2_2") (pintype "passive"))
      (node (ref "C274") (pin "1") (pinfunction "1_1") (pintype "passive"))
      (node (ref "C275") (pin "1") (pinfunction "1_1") (pintype "passive"))
      (node (ref "C276") (pin "1") (pinfunction "1_1") (pintype "passive"))
      (node (ref "C277") (pin "1") (pinfunction "1_1") (pintype "passive"))
      (node (ref "C278") (pin "1") (pinfunction "1_1") (pintype "passive"))
      (node (ref "C279") (pin "1") (pinfunction "1_1") (pintype "passive"))
      (node (ref "C280") (pin "1") (pinfunction "1_1") (pintype "passive"))
      (node (ref "C281") (pin "1") (pinfunction "1_1") (pintype "passive"))
      (node (ref "IC18") (pin "4") (pinfunction "A4_4") (pintype "passive"))
      (node (ref "IC18") (pin "5") (pinfunction "DIR3_5") (pintype "passive"))
      (node (ref "IC18") (pin "7") (pinfunction "OE_7") (pintype "passive"))
      (node (ref "IC18") (pin "8") (pinfunction "GND_8") (pintype "passive"))
      (node (ref "IC19") (pin "C2") (pinfunction "EN_C2") (pintype "passive"))
      (node (ref "IC19") (pin "D1") (pinfunction "GND_D1") (pintype "passive"))
      (node (ref "IC19") (pin "D2") (pinfunction "GND_D2") (pintype "passive"))
      (node (ref "IC19") (pin "D3") (pinfunction "DF_IN_D3") (pintype "passive"))
      (node (ref "IC20") (pin "5") (pinfunction "GND_5") (pintype "passive"))
      (node (ref "IC20") (pin "6") (pinfunction "GND_6") (pintype "passive"))
      (node (ref "IC20") (pin "7") (pinfunction "GND_7") (pintype "passive"))
      (node (ref "IC20") (pin "8") (pinfunction "GND_8") (pintype "passive"))
      (node (ref "IC21") (pin "5") (pinfunction "GND_5") (pintype "passive"))
      (node (ref "IC21") (pin "6") (pinfunction "GND_6") (pintype "passive"))
      (node (ref "IC21") (pin "7") (pinfunction "GND_7") (pintype "passive"))
      (node (ref "IC21") (pin "8") (pinfunction "GND_8") (pintype "passive"))
      (node (ref "IC22") (pin "10") (pinfunction "PGND_10") (pintype "passive"))
      (node (ref "IC22") (pin "11") (pinfunction "PGND_11") (pintype "passive"))
      (node (ref "IC22") (pin "12") (pinfunction "PGND_12") (pintype "passive"))
      (node (ref "IC22") (pin "13") (pinfunction "PGND_13") (pintype "passive"))
      (node (ref "IC22") (pin "25") (pinfunction "GND_25") (pintype "passive"))
      (node (ref "IC22") (pin "4") (pinfunction "GND_4") (pintype "passive"))
      (node (ref "IC22") (pin "8") (pinfunction "PGND_8") (pintype "passive"))
      (node (ref "IC22") (pin "9") (pinfunction "PGND_9") (pintype "passive"))
      (node (ref "IC23") (pin "11") (pinfunction "GND_11") (pintype "passive"))
      (node (ref "IC23") (pin "4") (pinfunction "PGND_4") (pintype "passive"))
      (node (ref "IC23") (pin "8") (pinfunction "GND_8") (pintype "passive"))
      (node (ref "IC24") (pin "5") (pinfunction "GND_5") (pintype "passive"))
      (node (ref "IC24") (pin "6") (pinfunction "GND_6") (pintype "passive"))
      (node (ref "IC24") (pin "7") (pinfunction "GND_7") (pintype "passive"))
      (node (ref "IC24") (pin "8") (pinfunction "GND_8") (pintype "passive"))
      (node (ref "IC25") (pin "10") (pinfunction "PGND_10") (pintype "passive"))
      (node (ref "IC25") (pin "11") (pinfunction "PGND_11") (pintype "passive"))
      (node (ref "IC25") (pin "12") (pinfunction "PGND_12") (pintype "passive"))
      (node (ref "IC25") (pin "13") (pinfunction "PGND_13") (pintype "passive"))
      (node (ref "IC25") (pin "25") (pinfunction "GND_25") (pintype "passive"))
      (node (ref "IC25") (pin "4") (pinfunction "GND_4") (pintype "passive"))
      (node (ref "IC25") (pin "8") (pinfunction "PGND_8") (pintype "passive"))
      (node (ref "IC25") (pin "9") (pinfunction "PGND_9") (pintype "passive"))
      (node (ref "IC26") (pin "5") (pinfunction "GND_5") (pintype "passive"))
      (node (ref "IC26") (pin "6") (pinfunction "GND_6") (pintype "passive"))
      (node (ref "IC26") (pin "7") (pinfunction "GND_7") (pintype "passive"))
      (node (ref "IC26") (pin "8") (pinfunction "GND_8") (pintype "passive"))
      (node (ref "IC27") (pin "5") (pinfunction "GND_5") (pintype "passive"))
      (node (ref "IC27") (pin "6") (pinfunction "GND_6") (pintype "passive"))
      (node (ref "IC27") (pin "7") (pinfunction "GND_7") (pintype "passive"))
      (node (ref "IC27") (pin "8") (pinfunction "GND_8") (pintype "passive"))
      (node (ref "IC28") (pin "5") (pinfunction "GND_5") (pintype "passive"))
      (node (ref "IC28") (pin "6") (pinfunction "GND_6") (pintype "passive"))
      (node (ref "IC28") (pin "7") (pinfunction "GND_7") (pintype "passive"))
      (node (ref "IC28") (pin "8") (pinfunction "GND_8") (pintype "passive"))
      (node (ref "IC29") (pin "3") (pinfunction "GND_3") (pintype "passive"))
      (node (ref "IC30") (pin "5") (pinfunction "GND_5") (pintype "passive"))
      (node (ref "IC30") (pin "6") (pinfunction "GND_6") (pintype "passive"))
      (node (ref "IC30") (pin "7") (pinfunction "GND_7") (pintype "passive"))
      (node (ref "IC30") (pin "8") (pinfunction "GND_8") (pintype "passive"))
      (node (ref "J15") (pin "2") (pinfunction "2_2") (pintype "passive"))
      (node (ref "J15") (pin "3") (pinfunction "3_3") (pintype "passive"))
      (node (ref "J16") (pin "1") (pinfunction "1_1") (pintype "passive"))
      (node (ref "LED8") (pin "3") (pinfunction "3_3") (pintype "power_in"))
      (node (ref "LEDS2") (pin "K2") (pinfunction "C_K2") (pintype "power_in"))
      (node (ref "MECH1") (pin "MH1") (pinfunction "MH1_MH1") (pintype "passive"))
      (node (ref "MECH2") (pin "MH1") (pinfunction "MH1_MH1") (pintype "passive"))
      (node (ref "MECH3") (pin "MH1") (pinfunction "MH1_MH1") (pintype "passive"))
      (node (ref "MECH4") (pin "MH1") (pinfunction "MH1_MH1") (pintype "passive"))
      (node (ref "R130") (pin "1") (pinfunction "1_1") (pintype "passive"))
      (node (ref "R135") (pin "1") (pinfunction "1_1") (pintype "passive"))
      (node (ref "R137") (pin "2") (pinfunction "2_2") (pintype "passive"))
      (node (ref "R138") (pin "1") (pinfunction "1_1") (pintype "passive"))
      (node (ref "R144") (pin "2") (pinfunction "2_2") (pintype "passive"))
      (node (ref "R150") (pin "2") (pinfunction "2_2") (pintype "passive"))
      (node (ref "R151") (pin "1") (pinfunction "1_1") (pintype "passive"))
      (node (ref "R152") (pin "1") (pinfunction "1_1") (pintype "passive"))
      (node (ref "R153") (pin "2") (pinfunction "2_2") (pintype "passive"))
      (node (ref "R159") (pin "1") (pinfunction "1_1") (pintype "passive"))
      (node (ref "R161") (pin "2") (pinfunction "2_2") (pintype "passive"))
      (node (ref "R164") (pin "1") (pinfunction "1_1") (pintype "passive"))
    )
    (net (code "12") (name "Net-(C237-Pad1)") (class "Default")
      (node (ref "C237") (pin "1") (pinfunction "1_1") (pintype "passive"))
      (node (ref "J15") (pin "1") (pinfunction "1_1") (pintype "passive"))
      (node (ref "J16") (pin "2") (pinfunction "2_2") (pintype "passive"))
      (node (ref "VD1") (pin "A") (pinfunction "A_A") (pintype "passive"))
    )
    (net (code "13") (name "Net-(C240-Pad2)") (class "Default")
      (node (ref "C240") (pin "2") (pinfunction "2_2") (pintype "passive"))
      (node (ref "IC22") (pin "14") (pinfunction "SW_14") (pintype "passive"))
      (node (ref "IC22") (pin "26") (pinfunction "SW_26") (pintype "passive"))
      (node (ref "IC22") (pin "5") (pinfunction "SW_5") (pintype "passive"))
      (node (ref "IC22") (pin "6") (pinfunction "SW_6") (pintype "passive"))
      (node (ref "IC22") (pin "7") (pinfunction "SW_7") (pintype "passive"))
      (node (ref "L1") (pin "1") (pinfunction "1_1") (pintype "passive"))
    )
    (net (code "14") (name "Net-(C253-Pad1)") (class "Default")
      (node (ref "C253") (pin "1") (pinfunction "1_1") (pintype "passive"))
      (node (ref "R139") (pin "1") (pinfunction "1_1") (pintype "passive"))
    )
    (net (code "15") (name "Net-(C259-Pad2)") (class "Default")
      (node (ref "C259") (pin "2") (pinfunction "2_2") (pintype "passive"))
      (node (ref "IC25") (pin "14") (pinfunction "SW_14") (pintype "passive"))
      (node (ref "IC25") (pin "26") (pinfunction "SW_26") (pintype "passive"))
      (node (ref "IC25") (pin "5") (pinfunction "SW_5") (pintype "passive"))
      (node (ref "IC25") (pin "6") (pinfunction "SW_6") (pintype "passive"))
      (node (ref "IC25") (pin "7") (pinfunction "SW_7") (pintype "passive"))
      (node (ref "L2") (pin "1") (pinfunction "1_1") (pintype "passive"))
    )
    (net (code "16") (name "Net-(C272-Pad1)") (class "Default")
      (node (ref "C272") (pin "1") (pinfunction "1_1") (pintype "passive"))
      (node (ref "R154") (pin "1") (pinfunction "1_1") (pintype "passive"))
    )
    (net (code "17") (name "Net-(C279-Pad2)") (class "Default")
      (node (ref "C279") (pin "2") (pinfunction "2_2") (pintype "passive"))
      (node (ref "FR59") (pin "2") (pinfunction "2_2") (pintype "passive"))
      (node (ref "R160") (pin "2") (pinfunction "2_2") (pintype "passive"))
    )
    (net (code "18") (name "Net-(IC20-ADJ)") (class "Default")
      (node (ref "IC20") (pin "4") (pinfunction "ADJ_4") (pintype "passive"))
      (node (ref "R129") (pin "2") (pinfunction "2_2") (pintype "passive"))
      (node (ref "R130") (pin "2") (pinfunction "2_2") (pintype "passive"))
    )
    (net (code "19") (name "Net-(IC20-OUT)") (class "Default")
      (node (ref "C228") (pin "2") (pinfunction "2_2") (pintype "passive"))
      (node (ref "IC20") (pin "3") (pinfunction "OUT_3") (pintype "passive"))
      (node (ref "R128") (pin "2") (pinfunction "2_2") (pintype "passive"))
      (node (ref "R129") (pin "1") (pinfunction "1_1") (pintype "passive"))
    )
    (net (code "20") (name "Net-(IC21-ADJ)") (class "Default")
      (node (ref "IC21") (pin "4") (pinfunction "ADJ_4") (pintype "passive"))
      (node (ref "R134") (pin "2") (pinfunction "2_2") (pintype "passive"))
      (node (ref "R135") (pin "2") (pinfunction "2_2") (pintype "passive"))
    )
    (net (code "21") (name "Net-(IC21-EN)") (class "Default")
      (node (ref "C243") (pin "2") (pinfunction "2_2") (pintype "passive"))
      (node (ref "FR54") (pin "2") (pinfunction "2_2") (pintype "passive"))
      (node (ref "IC21") (pin "1") (pinfunction "EN_1") (pintype "passive"))
      (node (ref "IC21") (pin "2") (pinfunction "IN_2") (pintype "passive"))
    )
    (net (code "22") (name "Net-(IC21-OUT)") (class "Default")
      (node (ref "C244") (pin "2") (pinfunction "2_2") (pintype "passive"))
      (node (ref "IC21") (pin "3") (pinfunction "OUT_3") (pintype "passive"))
      (node (ref "R132") (pin "2") (pinfunction "2_2") (pintype "passive"))
      (node (ref "R134") (pin "1") (pinfunction "1_1") (pintype "passive"))
    )
    (net (code "23") (name "Net-(IC22-BST)") (class "Default")
      (node (ref "C240") (pin "1") (pinfunction "1_1") (pintype "passive"))
      (node (ref "IC22") (pin "15") (pinfunction "BST_15") (pintype "passive"))
    )
    (net (code "24") (name "Net-(IC22-COMP)") (class "Default")
      (node (ref "C252") (pin "1") (pinfunction "1_1") (pintype "passive"))
      (node (ref "IC22") (pin "1") (pinfunction "COMP_1") (pintype "passive"))
      (node (ref "R139") (pin "2") (pinfunction "2_2") (pintype "passive"))
    )
    (net (code "25") (name "Net-(IC22-FB)") (class "Default")
      (node (ref "IC22") (pin "2") (pinfunction "FB_2") (pintype "passive"))
      (node (ref "R136") (pin "2") (pinfunction "2_2") (pintype "passive"))
      (node (ref "R138") (pin "2") (pinfunction "2_2") (pintype "passive"))
    )
    (net (code "26") (name "Net-(IC22-RT)") (class "Default")
      (node (ref "IC22") (pin "22") (pinfunction "RT_22") (pintype "passive"))
      (node (ref "R137") (pin "1") (pinfunction "1_1") (pintype "passive"))
    )
    (net (code "27") (name "Net-(IC22-SS)") (class "Default")
      (node (ref "C254") (pin "1") (pinfunction "1_1") (pintype "passive"))
      (node (ref "IC22") (pin "24") (pinfunction "SS_24") (pintype "passive"))
    )
    (net (code "28") (name "Net-(IC22-VREG)") (class "Default")
      (node (ref "C248") (pin "1") (pinfunction "1_1") (pintype "passive"))
      (node (ref "IC22") (pin "3") (pinfunction "VREG_3") (pintype "passive"))
    )
    (net (code "29") (name "Net-(IC23-S3)") (class "Default")
      (node (ref "IC23") (pin "7") (pinfunction "S3_7") (pintype "passive"))
      (node (ref "R142") (pin "2") (pinfunction "2_2") (pintype "passive"))
    )
    (net (code "30") (name "Net-(IC23-S5)") (class "Default")
      (node (ref "IC23") (pin "9") (pinfunction "S5_9") (pintype "passive"))
      (node (ref "R140") (pin "2") (pinfunction "2_2") (pintype "passive"))
    )
    (net (code "31") (name "Net-(IC24-ADJ)") (class "Default")
      (node (ref "IC24") (pin "4") (pinfunction "ADJ_4") (pintype "passive"))
      (node (ref "R143") (pin "2") (pinfunction "2_2") (pintype "passive"))
      (node (ref "R144") (pin "1") (pinfunction "1_1") (pintype "passive"))
    )
    (net (code "32") (name "Net-(IC24-EN)") (class "Default")
      (node (ref "C250") (pin "2") (pinfunction "2_2") (pintype "passive"))
      (node (ref "FR55") (pin "2") (pinfunction "2_2") (pintype "passive"))
      (node (ref "IC24") (pin "1") (pinfunction "EN_1") (pintype "passive"))
      (node (ref "IC24") (pin "2") (pinfunction "IN_2") (pintype "passive"))
    )
    (net (code "33") (name "Net-(IC24-OUT)") (class "Default")
      (node (ref "C251") (pin "2") (pinfunction "2_2") (pintype "passive"))
      (node (ref "IC24") (pin "3") (pinfunction "OUT_3") (pintype "passive"))
      (node (ref "R141") (pin "2") (pinfunction "2_2") (pintype "passive"))
      (node (ref "R143") (pin "1") (pinfunction "1_1") (pintype "passive"))
    )
    (net (code "34") (name "Net-(IC25-BST)") (class "Default")
      (node (ref "C259") (pin "1") (pinfunction "1_1") (pintype "passive"))
      (node (ref "IC25") (pin "15") (pinfunction "BST_15") (pintype "passive"))
    )
    (net (code "35") (name "Net-(IC25-COMP)") (class "Default")
      (node (ref "C271") (pin "1") (pinfunction "1_1") (pintype "passive"))
      (node (ref "IC25") (pin "1") (pinfunction "COMP_1") (pintype "passive"))
      (node (ref "R154") (pin "2") (pinfunction "2_2") (pintype "passive"))
    )
    (net (code "36") (name "Net-(IC25-FB)") (class "Default")
      (node (ref "IC25") (pin "2") (pinfunction "FB_2") (pintype "passive"))
      (node (ref "R149") (pin "2") (pinfunction "2_2") (pintype "passive"))
      (node (ref "R153") (pin "1") (pinfunction "1_1") (pintype "passive"))
    )
    (net (code "37") (name "Net-(IC25-RT)") (class "Default")
      (node (ref "IC25") (pin "22") (pinfunction "RT_22") (pintype "passive"))
      (node (ref "R150") (pin "1") (pinfunction "1_1") (pintype "passive"))
    )
    (net (code "38") (name "Net-(IC25-SS)") (class "Default")
      (node (ref "C273") (pin "1") (pinfunction "1_1") (pintype "passive"))
      (node (ref "IC25") (pin "24") (pinfunction "SS_24") (pintype "passive"))
    )
    (net (code "39") (name "Net-(IC25-VREG)") (class "Default")
      (node (ref "C268") (pin "1") (pinfunction "1_1") (pintype "passive"))
      (node (ref "IC25") (pin "3") (pinfunction "VREG_3") (pintype "passive"))
    )
    (net (code "40") (name "Net-(IC26-ADJ)") (class "Default")
      (node (ref "IC26") (pin "4") (pinfunction "ADJ_4") (pintype "passive"))
      (node (ref "R147") (pin "2") (pinfunction "2_2") (pintype "passive"))
      (node (ref "R151") (pin "2") (pinfunction "2_2") (pintype "passive"))
    )
    (net (code "41") (name "Net-(IC26-OUT)") (class "Default")
      (node (ref "C262") (pin "2") (pinfunction "2_2") (pintype "passive"))
      (node (ref "IC26") (pin "3") (pinfunction "OUT_3") (pintype "passive"))
      (node (ref "R145") (pin "2") (pinfunction "2_2") (pintype "passive"))
      (node (ref "R147") (pin "1") (pinfunction "1_1") (pintype "passive"))
    )
    (net (code "42") (name "Net-(IC27-ADJ)") (class "Default")
      (node (ref "IC27") (pin "4") (pinfunction "ADJ_4") (pintype "passive"))
      (node (ref "R148") (pin "2") (pinfunction "2_2") (pintype "passive"))
      (node (ref "R152") (pin "2") (pinfunction "2_2") (pintype "passive"))
    )
    (net (code "43") (name "Net-(IC27-EN)") (class "Default")
      (node (ref "C264") (pin "2") (pinfunction "2_2") (pintype "passive"))
      (node (ref "FR56") (pin "2") (pinfunction "2_2") (pintype "passive"))
      (node (ref "IC27") (pin "1") (pinfunction "EN_1") (pintype "passive"))
      (node (ref "IC27") (pin "2") (pinfunction "IN_2") (pintype "passive"))
    )
    (net (code "44") (name "Net-(IC27-OUT)") (class "Default")
      (node (ref "C265") (pin "2") (pinfunction "2_2") (pintype "passive"))
      (node (ref "IC27") (pin "3") (pinfunction "OUT_3") (pintype "passive"))
      (node (ref "R146") (pin "2") (pinfunction "2_2") (pintype "passive"))
      (node (ref "R148") (pin "1") (pinfunction "1_1") (pintype "passive"))
    )
    (net (code "45") (name "Net-(IC28-ADJ)") (class "Default")
      (node (ref "IC28") (pin "4") (pinfunction "ADJ_4") (pintype "passive"))
      (node (ref "R156") (pin "2") (pinfunction "2_2") (pintype "passive"))
      (node (ref "R159") (pin "2") (pinfunction "2_2") (pintype "passive"))
    )
    (net (code "46") (name "Net-(IC28-OUT)") (class "Default")
      (node (ref "C270") (pin "2") (pinfunction "2_2") (pintype "passive"))
      (node (ref "IC28") (pin "3") (pinfunction "OUT_3") (pintype "passive"))
      (node (ref "R155") (pin "2") (pinfunction "2_2") (pintype "passive"))
      (node (ref "R156") (pin "1") (pinfunction "1_1") (pintype "passive"))
    )
    (net (code "47") (name "Net-(IC29-ADJUST)") (class "Default")
      (node (ref "IC29") (pin "5") (pinfunction "ADJUST_5") (pintype "passive"))
      (node (ref "R158") (pin "2") (pinfunction "2_2") (pintype "passive"))
      (node (ref "R161") (pin "1") (pinfunction "1_1") (pintype "passive"))
    )
    (net (code "48") (name "Net-(IC29-IN)") (class "Default")
      (node (ref "C276") (pin "2") (pinfunction "2_2") (pintype "passive"))
      (node (ref "FR57") (pin "2") (pinfunction "2_2") (pintype "passive"))
      (node (ref "IC29") (pin "2") (pinfunction "IN_2") (pintype "passive"))
    )
    (net (code "49") (name "Net-(IC29-OUT)") (class "Default")
      (node (ref "C275") (pin "2") (pinfunction "2_2") (pintype "passive"))
      (node (ref "IC29") (pin "4") (pinfunction "OUT_4") (pintype "passive"))
      (node (ref "R157") (pin "2") (pinfunction "2_2") (pintype "passive"))
      (node (ref "R158") (pin "1") (pinfunction "1_1") (pintype "passive"))
    )
    (net (code "50") (name "Net-(IC30-ADJ)") (class "Default")
      (node (ref "IC30") (pin "4") (pinfunction "ADJ_4") (pintype "passive"))
      (node (ref "R162") (pin "2") (pinfunction "2_2") (pintype "passive"))
      (node (ref "R164") (pin "2") (pinfunction "2_2") (pintype "passive"))
    )
    (net (code "51") (name "Net-(IC30-EN)") (class "Default")
      (node (ref "C281") (pin "2") (pinfunction "2_2") (pintype "passive"))
      (node (ref "IC30") (pin "1") (pinfunction "EN_1") (pintype "passive"))
      (node (ref "R163") (pin "2") (pinfunction "2_2") (pintype "passive"))
      (node (ref "R165") (pin "1") (pinfunction "1_1") (pintype "passive"))
    )
    (net (code "52") (name "Net-(IC30-IN)") (class "Default")
      (node (ref "C280") (pin "2") (pinfunction "2_2") (pintype "passive"))
      (node (ref "FR58") (pin "2") (pinfunction "2_2") (pintype "passive"))
      (node (ref "IC30") (pin "2") (pinfunction "IN_2") (pintype "passive"))
    )
    (net (code "53") (name "Net-(IC30-OUT)") (class "Default")
      (node (ref "C277") (pin "2") (pinfunction "2_2") (pintype "passive"))
      (node (ref "FR59") (pin "1") (pinfunction "1_1") (pintype "passive"))
      (node (ref "IC30") (pin "3") (pinfunction "OUT_3") (pintype "passive"))
      (node (ref "R162") (pin "1") (pinfunction "1_1") (pintype "passive"))
    )
    (net (code "54") (name "Net-(LED1-Pad1)") (class "Default")
      (node (ref "LED1") (pin "1") (pinfunction "1_1") (pintype "power_in"))
      (node (ref "LED1") (pin "4") (pinfunction "4_4") (pintype "power_in"))
      (node (ref "LEDS1") (pin "A1") (pinfunction "A_A1") (pintype "power_in"))
      (node (ref "R126") (pin "2") (pinfunction "2_2") (pintype "passive"))
    )
    (net (code "55") (name "Net-(LED4-Pad1)") (class "Default")
      (node (ref "LED4") (pin "1") (pinfunction "1_1") (pintype "power_in"))
      (node (ref "LED4") (pin "4") (pinfunction "4_4") (pintype "power_in"))
      (node (ref "LEDS1") (pin "A2") (pinfunction "A_A2") (pintype "power_in"))
      (node (ref "R127") (pin "2") (pinfunction "2_2") (pintype "passive"))
    )
    (net (code "56") (name "Net-(LED5-Pad1)") (class "Default")
      (node (ref "LED5") (pin "1") (pinfunction "1_1") (pintype "power_in"))
      (node (ref "LED5") (pin "4") (pinfunction "4_4") (pintype "power_in"))
      (node (ref "LEDS2") (pin "A1") (pinfunction "A_A1") (pintype "power_in"))
      (node (ref "R131") (pin "2") (pinfunction "2_2") (pintype "passive"))
    )
    (net (code "57") (name "Net-(LED8-Pad1)") (class "Default")
      (node (ref "LED8") (pin "1") (pinfunction "1_1") (pintype "power_in"))
      (node (ref "LEDS2") (pin "A2") (pinfunction "A_A2") (pintype "power_in"))
      (node (ref "R133") (pin "2") (pinfunction "2_2") (pintype "passive"))
    )
    (net (code "58") (name "VCC1P2") (class "Default")
      (node (ref "C266") (pin "2") (pinfunction "2_2") (pintype "passive"))
      (node (ref "C267") (pin "2") (pinfunction "2_2") (pintype "passive"))
      (node (ref "L2") (pin "2") (pinfunction "2_2") (pintype "passive"))
      (node (ref "R149") (pin "1") (pinfunction "1_1") (pintype "passive"))
    )
    (net (code "59") (name "VCC1P4_LMS") (class "Default")
      (node (ref "R141") (pin "1") (pinfunction "1_1") (pintype "passive"))
    )
    (net (code "60") (name "VCC1P8") (class "Default")
      (node (ref "C229") (pin "2") (pinfunction "2_2") (pintype "passive"))
      (node (ref "IC18") (pin "14") (pinfunction "VCCA_14") (pintype "passive"))
      (node (ref "IC18") (pin "15") (pinfunction "DIR1_15") (pintype "passive"))
      (node (ref "IC18") (pin "16") (pinfunction "DIR2_16") (pintype "passive"))
      (node (ref "IC18") (pin "6") (pinfunction "DIR4_6") (pintype "passive"))
      (node (ref "R155") (pin "1") (pinfunction "1_1") (pintype "passive"))
    )
    (net (code "61") (name "VCC1P8_DDR2") (class "Default")
      (node (ref "C247") (pin "2") (pinfunction "2_2") (pintype "passive"))
      (node (ref "IC23") (pin "1") (pinfunction "VDDQSNS_1") (pintype "passive"))
      (node (ref "IC23") (pin "2") (pinfunction "VLDOIN_2") (pintype "passive"))
      (node (ref "R145") (pin "1") (pinfunction "1_1") (pintype "passive"))
    )
    (net (code "62") (name "VCC1P8_LMS") (class "Default")
      (node (ref "R132") (pin "1") (pinfunction "1_1") (pintype "passive"))
    )
    (net (code "63") (name "VCC1P25_LMS") (class "Default")
      (node (ref "R146") (pin "1") (pinfunction "1_1") (pintype "passive"))
    )
    (net (code "64") (name "VCC1P25_LMS_DIG") (class "Default")
      (node (ref "R157") (pin "1") (pinfunction "1_1") (pintype "passive"))
    )
    (net (code "65") (name "VCC2P5") (class "Default")
      (node (ref "R125") (pin "2") (pinfunction "2_2") (pintype "passive"))
      (node (ref "R128") (pin "1") (pinfunction "1_1") (pintype "passive"))
      (node (ref "R163") (pin "1") (pinfunction "1_1") (pintype "passive"))
    )
    (net (code "66") (name "VCC3P3") (class "Default")
      (node (ref "C227") (pin "2") (pinfunction "2_2") (pintype "passive"))
      (node (ref "C230") (pin "2") (pinfunction "2_2") (pintype "passive"))
      (node (ref "C242") (pin "2") (pinfunction "2_2") (pintype "passive"))
      (node (ref "C245") (pin "2") (pinfunction "2_2") (pintype "passive"))
      (node (ref "C246") (pin "2") (pinfunction "2_2") (pintype "passive"))
      (node (ref "C249") (pin "2") (pinfunction "2_2") (pintype "passive"))
      (node (ref "C257") (pin "2") (pinfunction "2_2") (pintype "passive"))
      (node (ref "C261") (pin "2") (pinfunction "2_2") (pintype "passive"))
      (node (ref "C263") (pin "2") (pinfunction "2_2") (pintype "passive"))
      (node (ref "C269") (pin "2") (pinfunction "2_2") (pintype "passive"))
      (node (ref "C274") (pin "2") (pinfunction "2_2") (pintype "passive"))
      (node (ref "FR54") (pin "1") (pinfunction "1_1") (pintype "passive"))
      (node (ref "FR55") (pin "1") (pinfunction "1_1") (pintype "passive"))
      (node (ref "FR56") (pin "1") (pinfunction "1_1") (pintype "passive"))
      (node (ref "FR57") (pin "1") (pinfunction "1_1") (pintype "passive"))
      (node (ref "IC18") (pin "13") (pinfunction "VCCB_13") (pintype "passive"))
      (node (ref "IC20") (pin "1") (pinfunction "EN_1") (pintype "passive"))
      (node (ref "IC20") (pin "2") (pinfunction "IN_2") (pintype "passive"))
      (node (ref "IC23") (pin "10") (pinfunction "VIN_10") (pintype "passive"))
      (node (ref "IC26") (pin "1") (pinfunction "EN_1") (pintype "passive"))
      (node (ref "IC26") (pin "2") (pinfunction "IN_2") (pintype "passive"))
      (node (ref "IC28") (pin "1") (pinfunction "EN_1") (pintype "passive"))
      (node (ref "IC28") (pin "2") (pinfunction "IN_2") (pintype "passive"))
      (node (ref "L1") (pin "2") (pinfunction "2_2") (pintype "passive"))
      (node (ref "R123") (pin "2") (pinfunction "2_2") (pintype "passive"))
      (node (ref "R133") (pin "1") (pinfunction "1_1") (pintype "passive"))
      (node (ref "R136") (pin "1") (pinfunction "1_1") (pintype "passive"))
      (node (ref "R140") (pin "1") (pinfunction "1_1") (pintype "passive"))
      (node (ref "R142") (pin "1") (pinfunction "1_1") (pintype "passive"))
    )
    (net (code "67") (name "VCC3P3_CLK") (class "Default")
      (node (ref "R160") (pin "1") (pinfunction "1_1") (pintype "passive"))
    )
    (net (code "68") (name "VCC5P0_USB") (class "Default")
      (node (ref "C239") (pin "2") (pinfunction "2_2") (pintype "passive"))
      (node (ref "IC19") (pin "A1") (pinfunction "Vbus_A1") (pintype "passive"))
      (node (ref "IC19") (pin "B1") (pinfunction "Vbus_B1") (pintype "passive"))
      (node (ref "IC19") (pin "C1") (pinfunction "Vbus_C1") (pintype "passive"))
      (node (ref "R124") (pin "2") (pinfunction "2_2") (pintype "passive"))
    )
    (net (code "69") (name "VCC_EXT") (class "Default")
      (node (ref "C238") (pin "2") (pinfunction "2_2") (pintype "passive"))
      (node (ref "IC19") (pin "A4") (pinfunction "Vin_A4") (pintype "passive"))
      (node (ref "IC19") (pin "B4") (pinfunction "Vin_B4") (pintype "passive"))
      (node (ref "IC19") (pin "C4") (pinfunction "Vin_C4") (pintype "passive"))
      (node (ref "R122") (pin "2") (pinfunction "2_2") (pintype "passive"))
      (node (ref "VD1") (pin "K") (pinfunction "K_K") (pintype "passive"))
    )
    (net (code "70") (name "VCC_INT") (class "Default")
      (node (ref "C231") (pin "2") (pinfunction "2_2") (pintype "passive"))
      (node (ref "C232") (pin "2") (pinfunction "2_2") (pintype "passive"))
      (node (ref "C233") (pin "2") (pinfunction "2_2") (pintype "passive"))
      (node (ref "C234") (pin "2") (pinfunction "2_2") (pintype "passive"))
      (node (ref "C235") (pin "2") (pinfunction "2_2") (pintype "passive"))
      (node (ref "C236") (pin "1") (pinfunction "1_1") (pintype "passive"))
      (node (ref "C241") (pin "2") (pinfunction "2_2") (pintype "passive"))
      (node (ref "C260") (pin "2") (pinfunction "2_2") (pintype "passive"))
      (node (ref "C278") (pin "2") (pinfunction "2_2") (pintype "passive"))
      (node (ref "FR58") (pin "1") (pinfunction "1_1") (pintype "passive"))
      (node (ref "IC19") (pin "A2") (pinfunction "Vout_A2") (pintype "passive"))
      (node (ref "IC19") (pin "A3") (pinfunction "Vout_A3") (pintype "passive"))
      (node (ref "IC19") (pin "B3") (pinfunction "Vout_B3") (pintype "passive"))
      (node (ref "IC19") (pin "C3") (pinfunction "Vout_C3") (pintype "passive"))
      (node (ref "IC22") (pin "16") (pinfunction "PVIN_16") (pintype "passive"))
      (node (ref "IC22") (pin "17") (pinfunction "PVIN_17") (pintype "passive"))
      (node (ref "IC22") (pin "18") (pinfunction "PVIN_18") (pintype "passive"))
      (node (ref "IC22") (pin "19") (pinfunction "PVIN_19") (pintype "passive"))
      (node (ref "IC22") (pin "20") (pinfunction "EN_20") (pintype "passive"))
      (node (ref "IC25") (pin "16") (pinfunction "PVIN_16") (pintype "passive"))
      (node (ref "IC25") (pin "17") (pinfunction "PVIN_17") (pintype "passive"))
      (node (ref "IC25") (pin "18") (pinfunction "PVIN_18") (pintype "passive"))
      (node (ref "IC25") (pin "19") (pinfunction "PVIN_19") (pintype "passive"))
      (node (ref "IC25") (pin "20") (pinfunction "EN_20") (pintype "passive"))
      (node (ref "J16") (pin "3") (pinfunction "3_3") (pintype "passive"))
      (node (ref "R122") (pin "1") (pinfunction "1_1") (pintype "passive"))
      (node (ref "R124") (pin "1") (pinfunction "1_1") (pintype "passive"))
      (node (ref "R165") (pin "2") (pinfunction "2_2") (pintype "passive"))
    )
    (net (code "71") (name "VDIO_LMS") (class "Default")
      (node (ref "C225") (pin "2") (pinfunction "2_2") (pintype "passive"))
      (node (ref "C226") (pin "1") (pinfunction "1_1") (pintype "passive"))
      (node (ref "FR53") (pin "2") (pinfunction "2_2") (pintype "passive"))
    )
    (net (code "72") (name "VDIO_LMS_FPGA") (class "Default")
      (node (ref "FR53") (pin "1") (pinfunction "1_1") (pintype "passive"))
      (node (ref "R123") (pin "1") (pinfunction "1_1") (pintype "passive"))
      (node (ref "R125") (pin "1") (pinfunction "1_1") (pintype "passive"))
    )
    (net (code "73") (name "VREF_DDR2") (class "Default")
      (node (ref "C258") (pin "1") (pinfunction "1_1") (pintype "passive"))
      (node (ref "IC23") (pin "6") (pinfunction "VTTREF_6") (pintype "passive"))
    )
    (net (code "74") (name "VTT_DDR2") (class "Default")
      (node (ref "C255") (pin "2") (pinfunction "2_2") (pintype "passive"))
      (node (ref "C256") (pin "2") (pinfunction "2_2") (pintype "passive"))
      (node (ref "IC23") (pin "3") (pinfunction "VTT_3") (pintype "passive"))
      (node (ref "IC23") (pin "5") (pinfunction "VTTSNS_5") (pintype "passive"))
    )
    (net (code "75") (name "unconnected-(F1-Pad1)") (class "Default")
      (node (ref "F1") (pin "1") (pintype "passive+no_connect"))
    )
    (net (code "76") (name "unconnected-(F2-Pad1)") (class "Default")
      (node (ref "F2") (pin "1") (pintype "passive+no_connect"))
    )
    (net (code "77") (name "unconnected-(F3-Pad1)") (class "Default")
      (node (ref "F3") (pin "1") (pintype "passive+no_connect"))
    )
    (net (code "78") (name "unconnected-(F4-Pad1)") (class "Default")
      (node (ref "F4") (pin "1") (pintype "passive+no_connect"))
    )
    (net (code "79") (name "unconnected-(IC18-B4-Pad9)") (class "Default")
      (node (ref "IC18") (pin "9") (pinfunction "B4_9") (pintype "passive+no_connect"))
    )
    (net (code "80") (name "unconnected-(IC19-Other_Vin_AVA-PadB2)") (class "Default")
      (node (ref "IC19") (pin "B2") (pinfunction "Other_Vin_AVA_B2") (pintype "passive+no_connect"))
    )
    (net (code "81") (name "unconnected-(IC19-Vin_SEL-PadD4)") (class "Default")
      (node (ref "IC19") (pin "D4") (pinfunction "Vin_SEL_D4") (pintype "passive+no_connect"))
    )
    (net (code "82") (name "unconnected-(IC22-PGOOD-Pad21)") (class "Default")
      (node (ref "IC22") (pin "21") (pinfunction "PGOOD_21") (pintype "passive+no_connect"))
    )
    (net (code "83") (name "unconnected-(IC22-SYNC-Pad23)") (class "Default")
      (node (ref "IC22") (pin "23") (pinfunction "SYNC_23") (pintype "passive+no_connect"))
    )
    (net (code "84") (name "unconnected-(IC25-PGOOD-Pad21)") (class "Default")
      (node (ref "IC25") (pin "21") (pinfunction "PGOOD_21") (pintype "passive+no_connect"))
    )
    (net (code "85") (name "unconnected-(IC25-SYNC-Pad23)") (class "Default")
      (node (ref "IC25") (pin "23") (pinfunction "SYNC_23") (pintype "passive+no_connect"))
    )
    (net (code "86") (name "unconnected-(IC29-NC-Pad1)") (class "Default")
      (node (ref "IC29") (pin "1") (pinfunction "NC_1") (pintype "passive+no_connect"))
    )
    (net (code "87") (name "unconnected-(LED2-C-PadK)") (class "Default")
      (node (ref "LED2") (pin "K") (pinfunction "C_K") (pintype "power_in+no_connect"))
    )
    (net (code "88") (name "unconnected-(LED2-PadA)") (class "Default")
      (node (ref "LED2") (pin "A") (pinfunction "A_A") (pintype "power_in+no_connect"))
    )
    (net (code "89") (name "unconnected-(LED3-C-PadK)") (class "Default")
      (node (ref "LED3") (pin "K") (pinfunction "C_K") (pintype "power_in+no_connect"))
    )
    (net (code "90") (name "unconnected-(LED3-PadA)") (class "Default")
      (node (ref "LED3") (pin "A") (pinfunction "A_A") (pintype "power_in+no_connect"))
    )
    (net (code "91") (name "unconnected-(LED6-C-PadK)") (class "Default")
      (node (ref "LED6") (pin "K") (pinfunction "C_K") (pintype "power_in+no_connect"))
    )
    (net (code "92") (name "unconnected-(LED6-PadA)") (class "Default")
      (node (ref "LED6") (pin "A") (pinfunction "A_A") (pintype "power_in+no_connect"))
    )
    (net (code "93") (name "unconnected-(LED7-C-PadK)") (class "Default")
      (node (ref "LED7") (pin "K") (pinfunction "C_K") (pintype "power_in+no_connect"))
    )
    (net (code "94") (name "unconnected-(LED7-PadA)") (class "Default")
      (node (ref "LED7") (pin "A") (pinfunction "A_A") (pintype "power_in+no_connect"))
    )
    (net (code "95") (name "unconnected-(LED8-Pad2)") (class "Default")
      (node (ref "LED8") (pin "2") (pinfunction "2_2") (pintype "power_in+no_connect"))
    )
    (net (code "96") (name "unconnected-(LED8-Pad4)") (class "Default")
      (node (ref "LED8") (pin "4") (pinfunction "4_4") (pintype "power_in+no_connect"))
    )
  )
)
